# shield_bigfpga.net
KiCad netlist of a schematic drawn in EAGLE
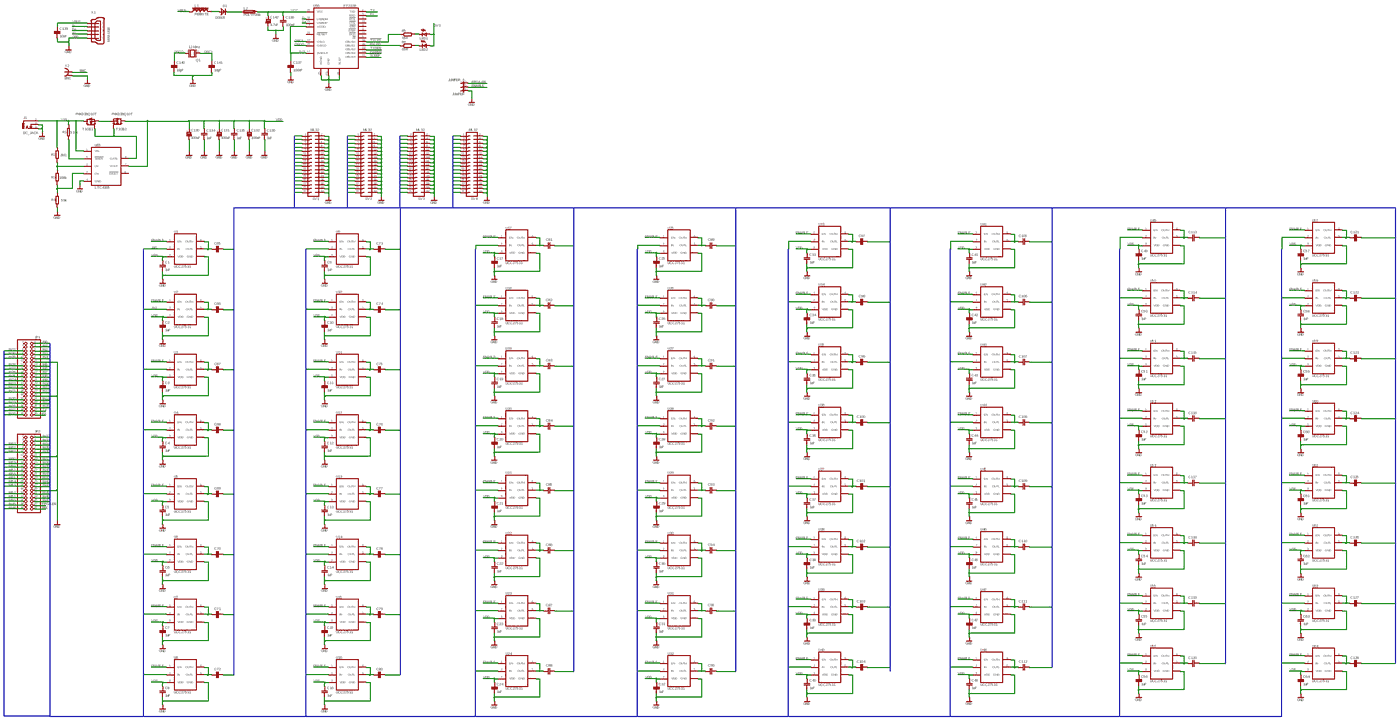
[diagram p0: schematic, sheet 1, overview]
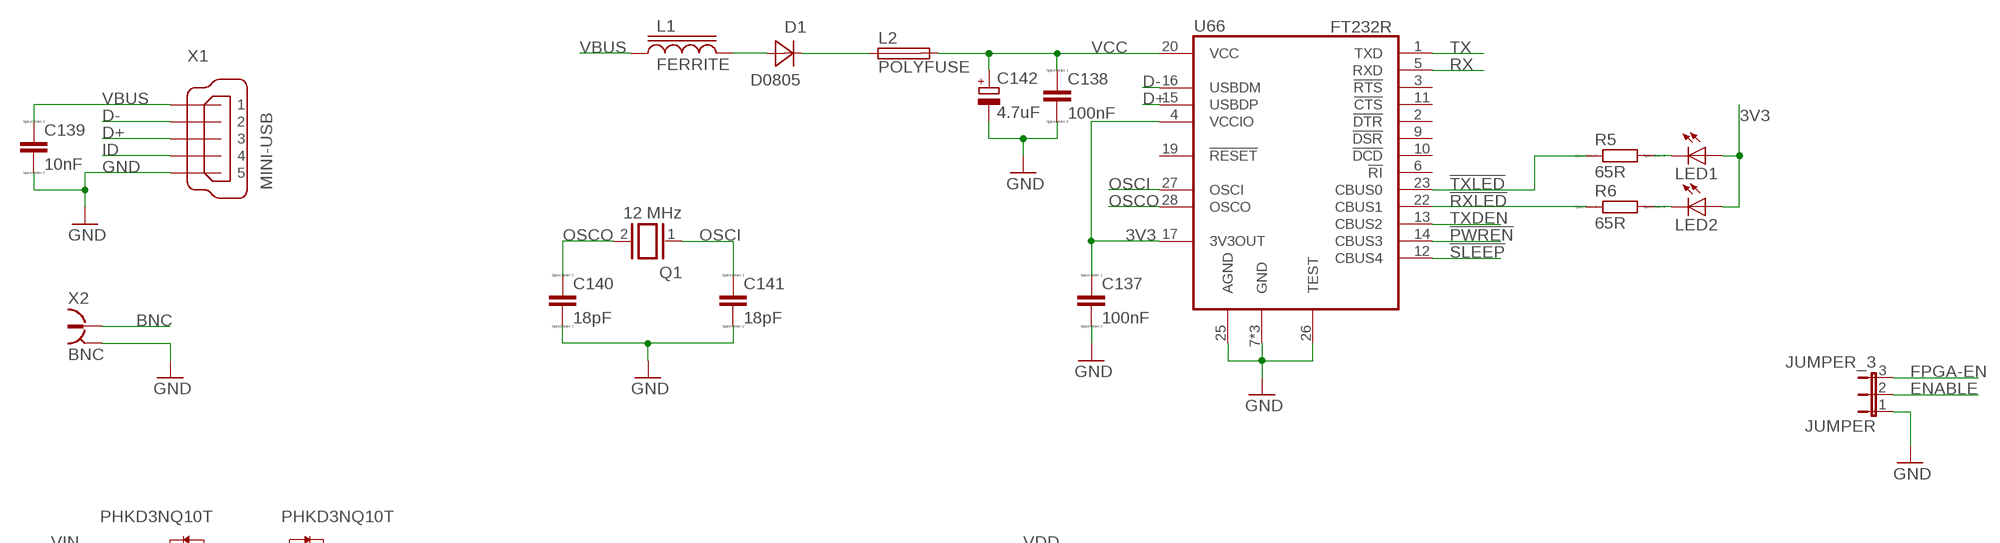
[diagram p1: schematic, sheet 1, part 1 of 4]
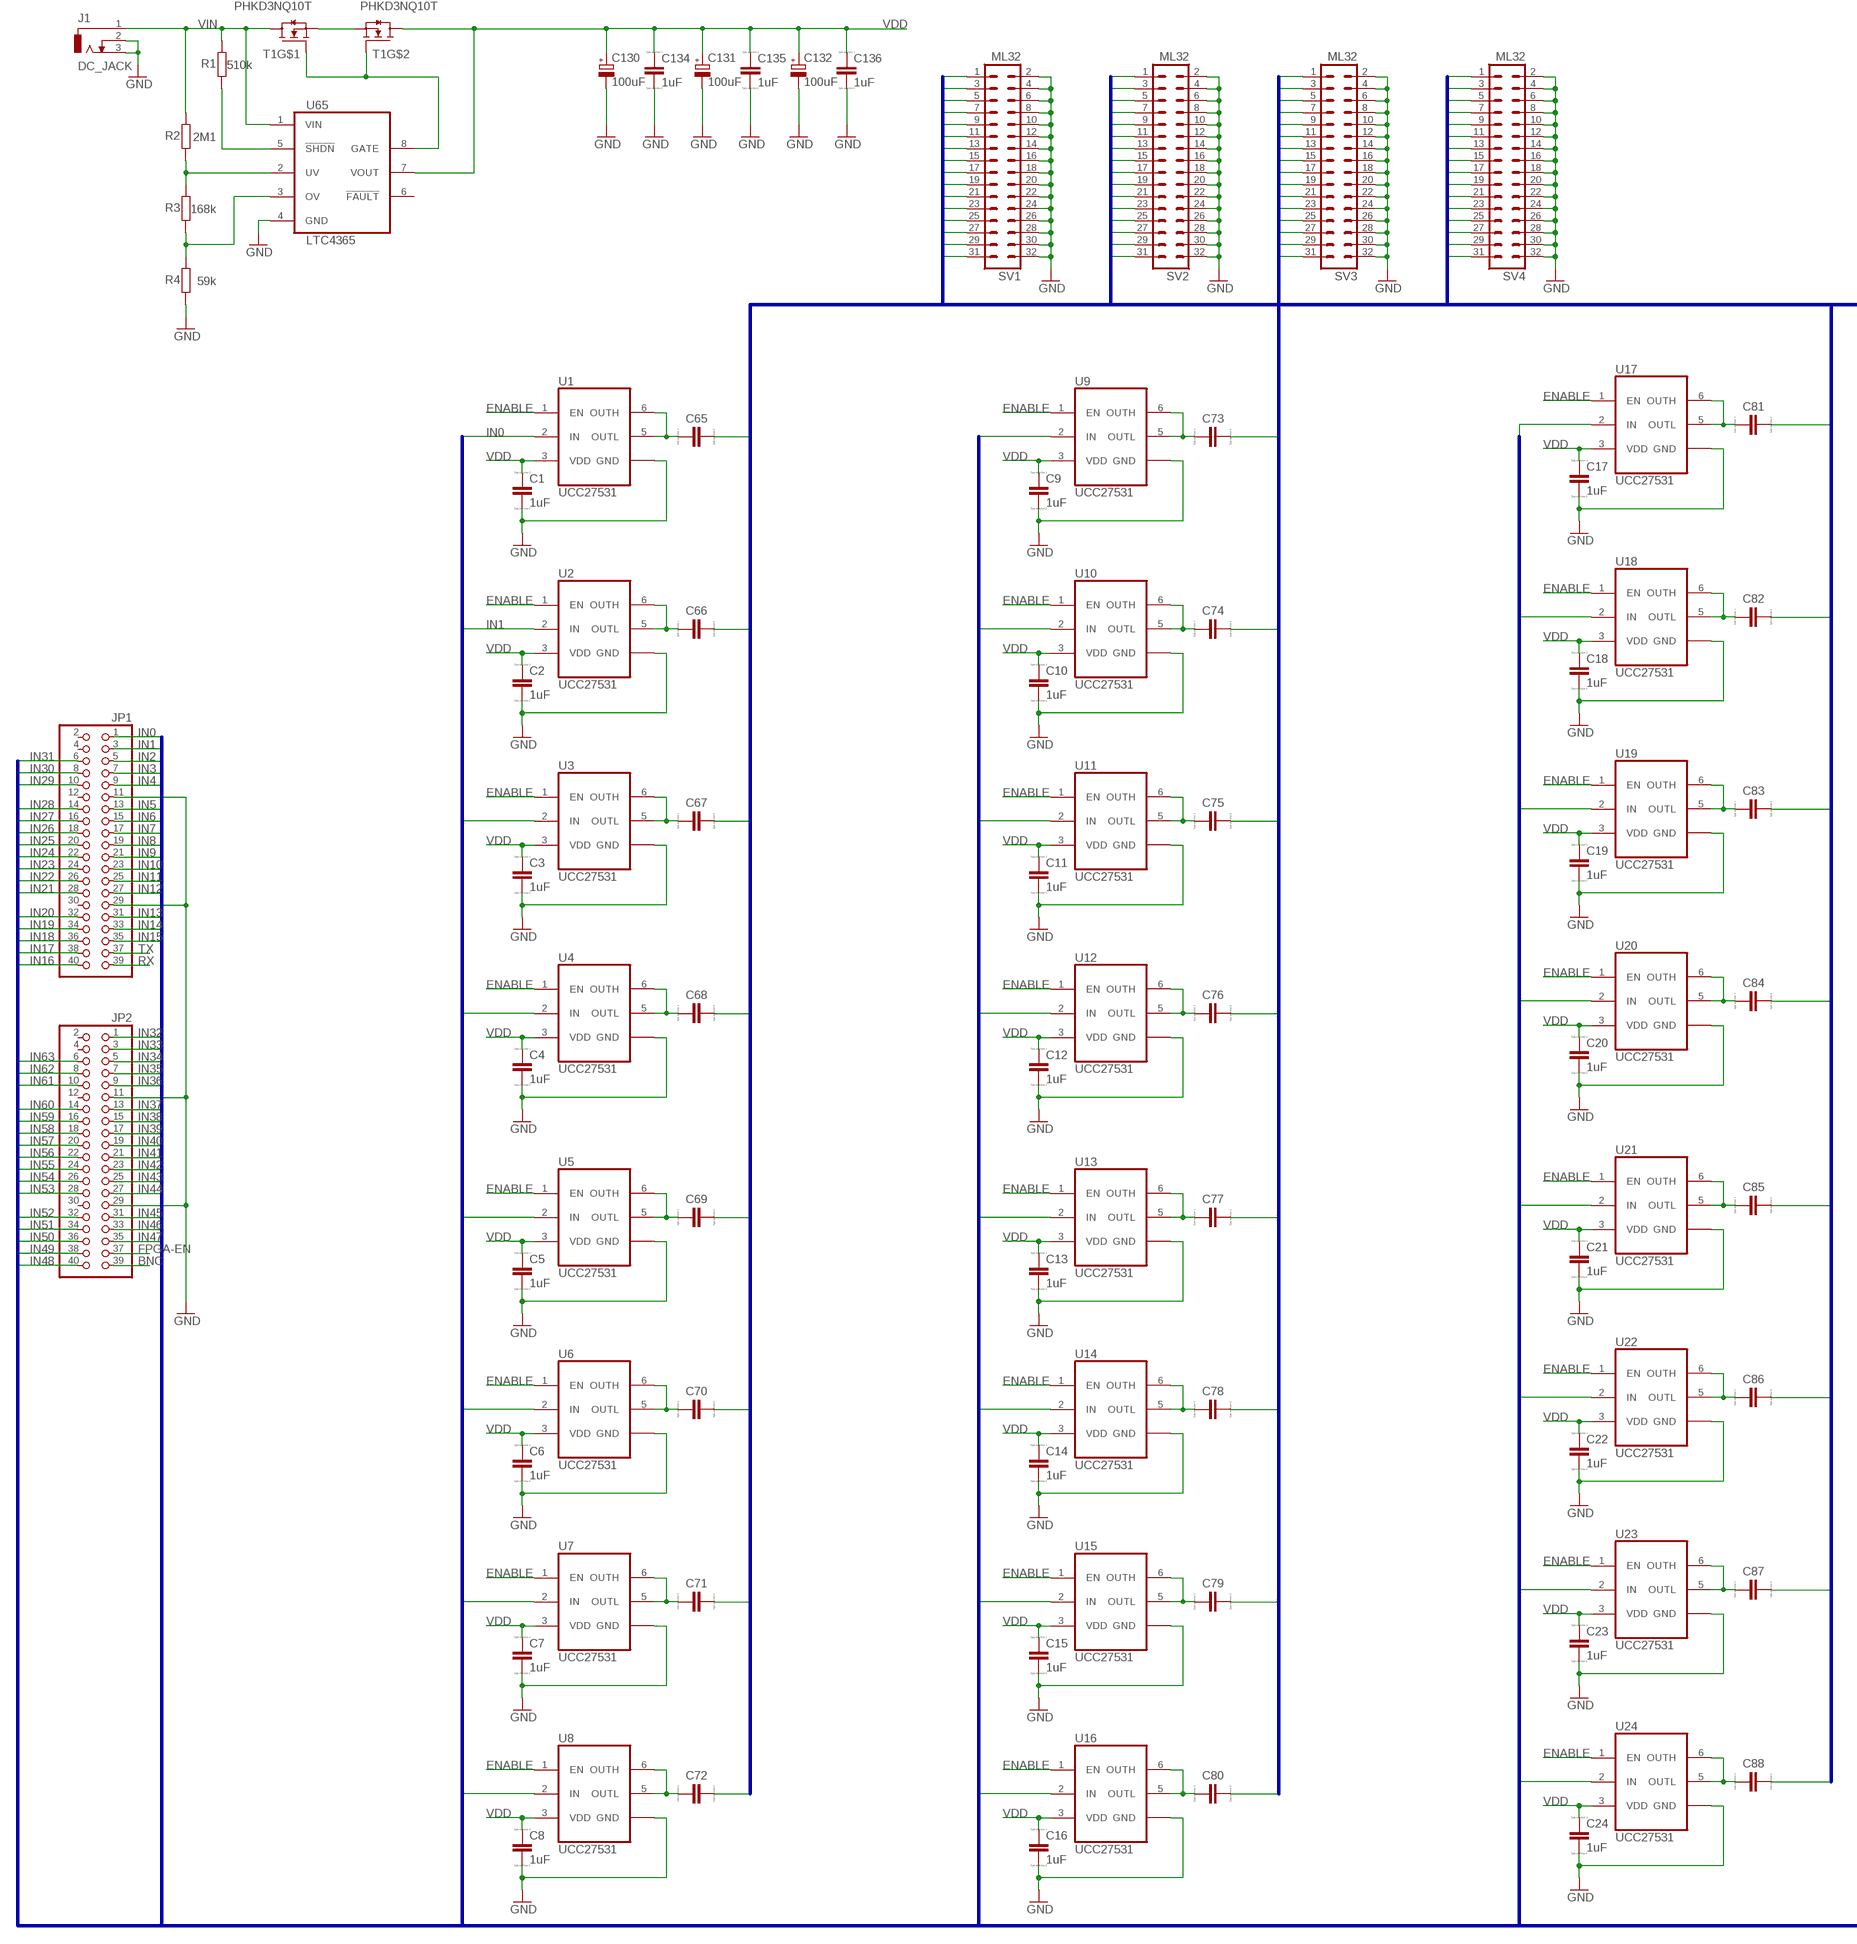
[diagram p2: schematic, sheet 1, part 2 of 4]
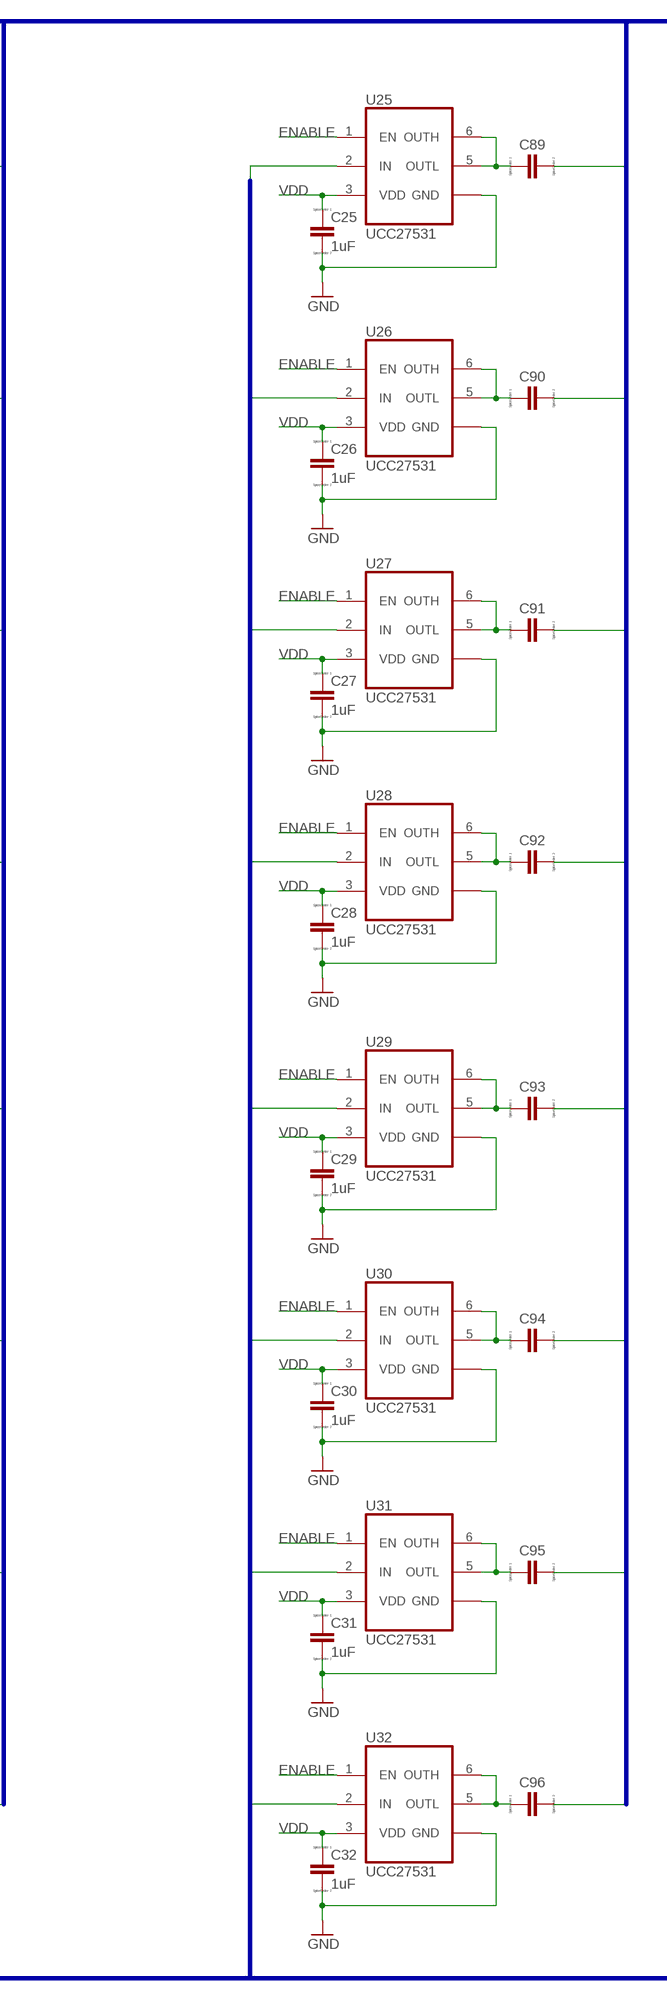
[diagram p3: schematic, sheet 1, part 3 of 4]
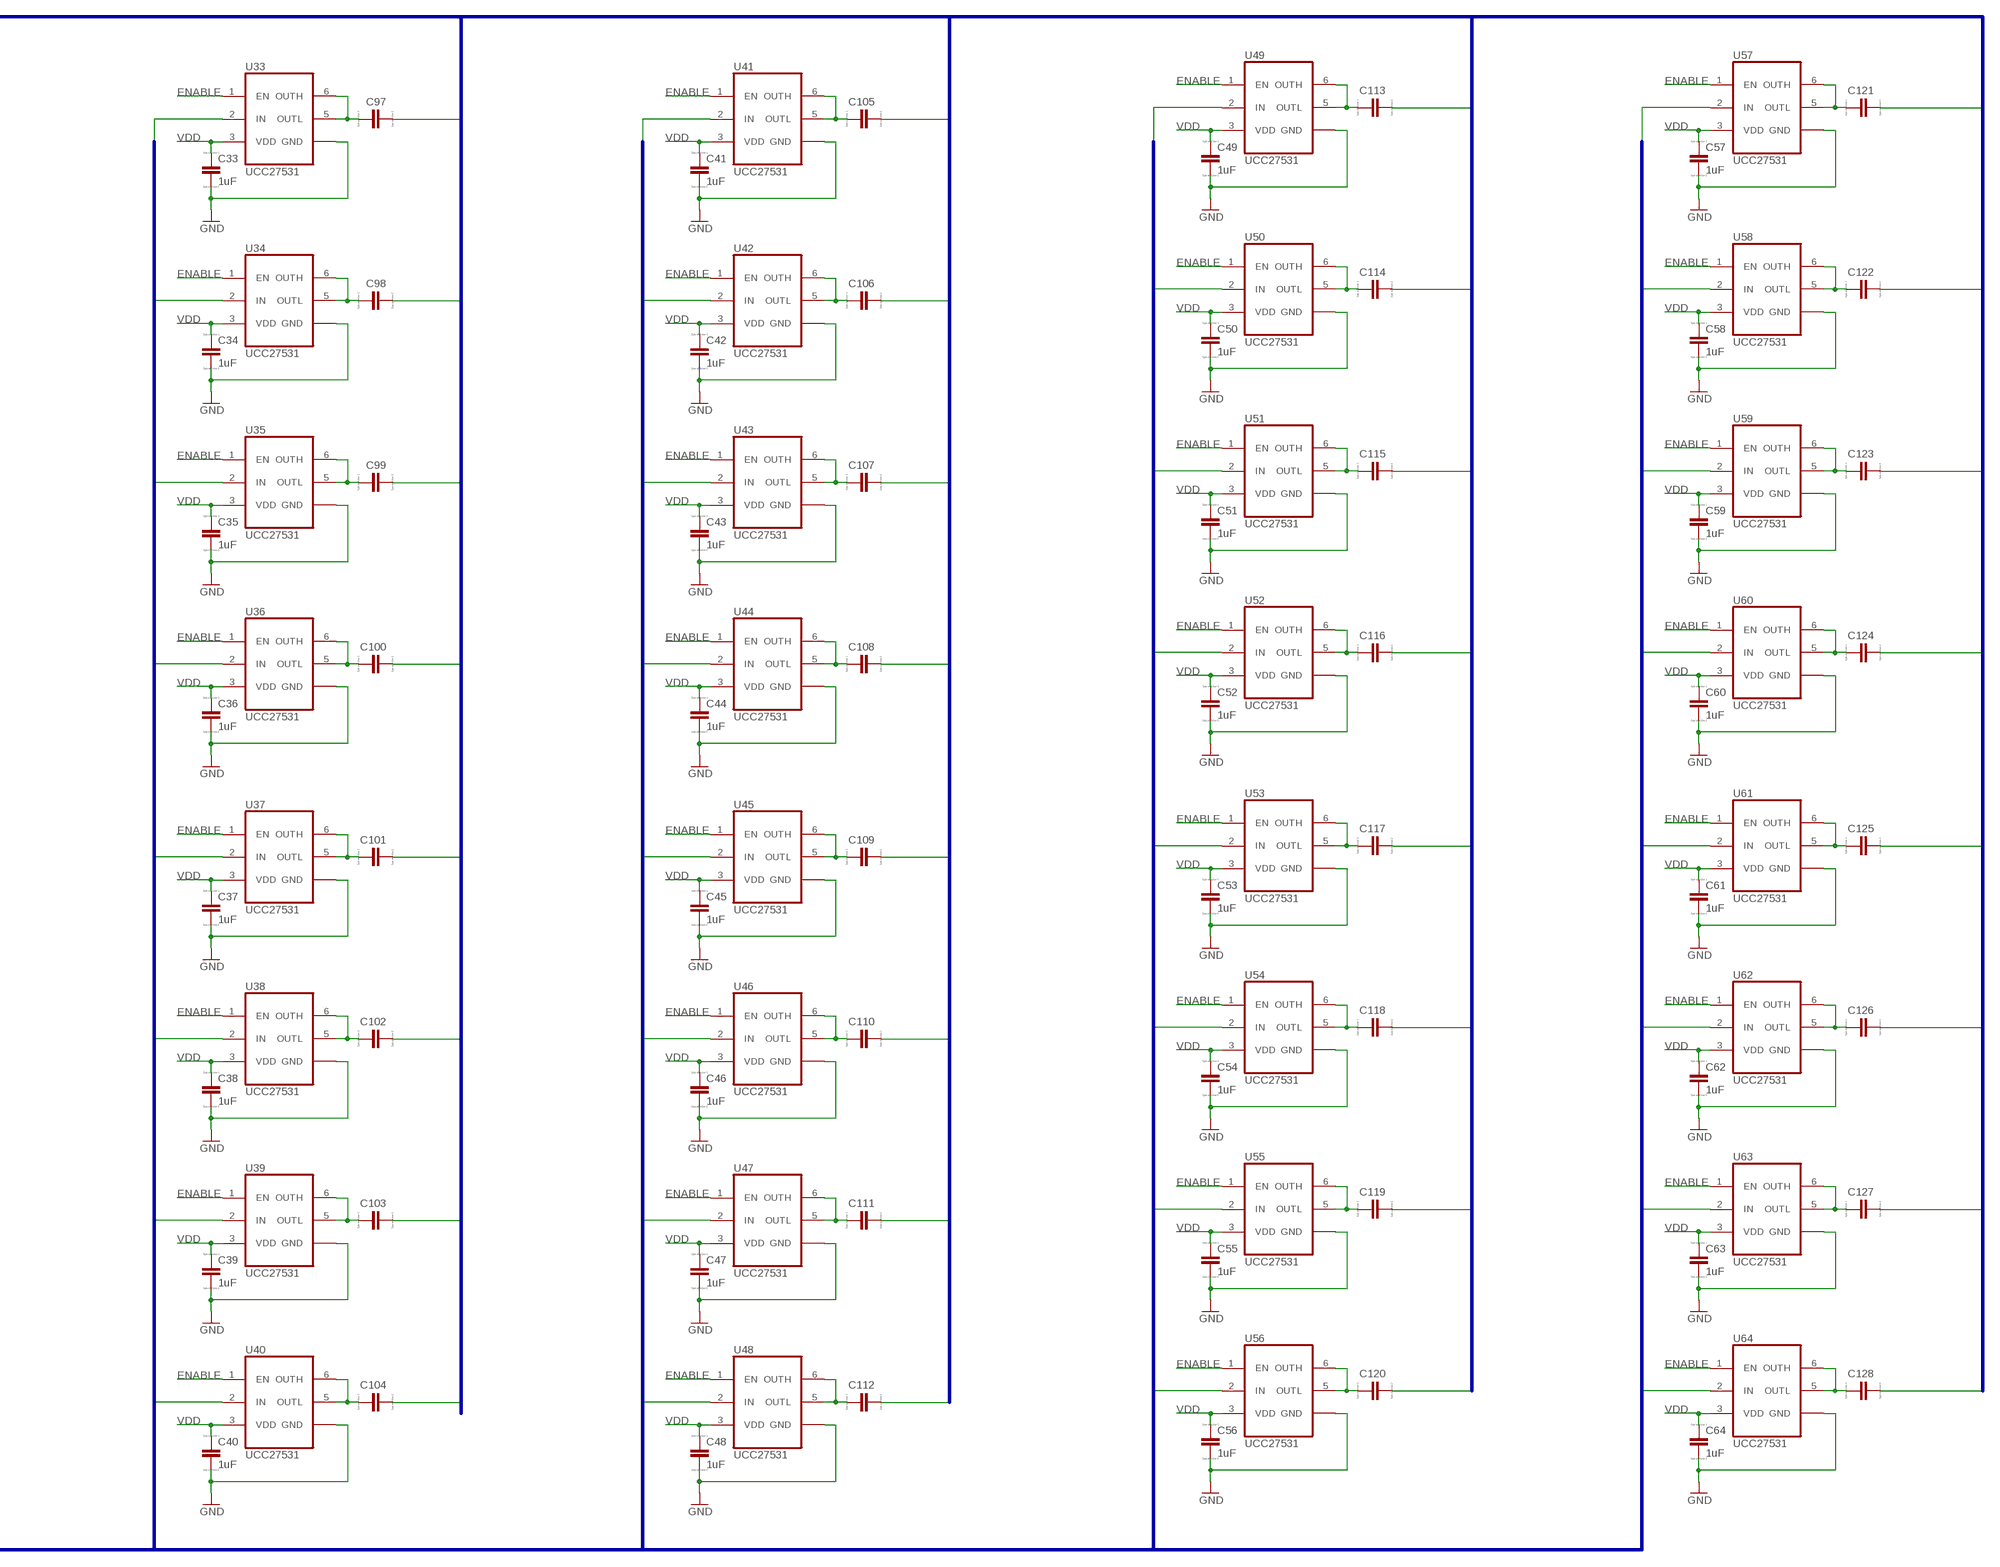
[diagram p4: schematic, sheet 1, part 4 of 4]

(export (version "E")
  (design (tool "Eeschema 10.0.6"))
  (components
    (comp (ref "C1")
      (value "1uF")
      (footprint "eagle-import:C0805")
      (libsource (lib "eagle-import") (part "C"))
    )
    (comp (ref "C2")
      (value "1uF")
      (footprint "eagle-import:C0805")
      (libsource (lib "eagle-import") (part "C"))
    )
    (comp (ref "C3")
      (value "1uF")
      (footprint "eagle-import:C0805")
      (libsource (lib "eagle-import") (part "C"))
    )
    (comp (ref "C4")
      (value "1uF")
      (footprint "eagle-import:C0805")
      (libsource (lib "eagle-import") (part "C"))
    )
    (comp (ref "C5")
      (value "1uF")
      (footprint "eagle-import:C0805")
      (libsource (lib "eagle-import") (part "C"))
    )
    (comp (ref "C6")
      (value "1uF")
      (footprint "eagle-import:C0805")
      (libsource (lib "eagle-import") (part "C"))
    )
    (comp (ref "C7")
      (value "1uF")
      (footprint "eagle-import:C0805")
      (libsource (lib "eagle-import") (part "C"))
    )
    (comp (ref "C8")
      (value "1uF")
      (footprint "eagle-import:C0805")
      (libsource (lib "eagle-import") (part "C"))
    )
    (comp (ref "C9")
      (value "1uF")
      (footprint "eagle-import:C0805")
      (libsource (lib "eagle-import") (part "C"))
    )
    (comp (ref "C10")
      (value "1uF")
      (footprint "eagle-import:C0805")
      (libsource (lib "eagle-import") (part "C"))
    )
    (comp (ref "C11")
      (value "1uF")
      (footprint "eagle-import:C0805")
      (libsource (lib "eagle-import") (part "C"))
    )
    (comp (ref "C12")
      (value "1uF")
      (footprint "eagle-import:C0805")
      (libsource (lib "eagle-import") (part "C"))
    )
    (comp (ref "C13")
      (value "1uF")
      (footprint "eagle-import:C0805")
      (libsource (lib "eagle-import") (part "C"))
    )
    (comp (ref "C14")
      (value "1uF")
      (footprint "eagle-import:C0805")
      (libsource (lib "eagle-import") (part "C"))
    )
    (comp (ref "C15")
      (value "1uF")
      (footprint "eagle-import:C0805")
      (libsource (lib "eagle-import") (part "C"))
    )
    (comp (ref "C16")
      (value "1uF")
      (footprint "eagle-import:C0805")
      (libsource (lib "eagle-import") (part "C"))
    )
    (comp (ref "C17")
      (value "1uF")
      (footprint "eagle-import:C0805")
      (libsource (lib "eagle-import") (part "C"))
    )
    (comp (ref "C18")
      (value "1uF")
      (footprint "eagle-import:C0805")
      (libsource (lib "eagle-import") (part "C"))
    )
    (comp (ref "C19")
      (value "1uF")
      (footprint "eagle-import:C0805")
      (libsource (lib "eagle-import") (part "C"))
    )
    (comp (ref "C20")
      (value "1uF")
      (footprint "eagle-import:C0805")
      (libsource (lib "eagle-import") (part "C"))
    )
    (comp (ref "C21")
      (value "1uF")
      (footprint "eagle-import:C0805")
      (libsource (lib "eagle-import") (part "C"))
    )
    (comp (ref "C22")
      (value "1uF")
      (footprint "eagle-import:C0805")
      (libsource (lib "eagle-import") (part "C"))
    )
    (comp (ref "C23")
      (value "1uF")
      (footprint "eagle-import:C0805")
      (libsource (lib "eagle-import") (part "C"))
    )
    (comp (ref "C24")
      (value "1uF")
      (footprint "eagle-import:C0805")
      (libsource (lib "eagle-import") (part "C"))
    )
    (comp (ref "C25")
      (value "1uF")
      (footprint "eagle-import:C0805")
      (libsource (lib "eagle-import") (part "C"))
    )
    (comp (ref "C26")
      (value "1uF")
      (footprint "eagle-import:C0805")
      (libsource (lib "eagle-import") (part "C"))
    )
    (comp (ref "C27")
      (value "1uF")
      (footprint "eagle-import:C0805")
      (libsource (lib "eagle-import") (part "C"))
    )
    (comp (ref "C28")
      (value "1uF")
      (footprint "eagle-import:C0805")
      (libsource (lib "eagle-import") (part "C"))
    )
    (comp (ref "C29")
      (value "1uF")
      (footprint "eagle-import:C0805")
      (libsource (lib "eagle-import") (part "C"))
    )
    (comp (ref "C30")
      (value "1uF")
      (footprint "eagle-import:C0805")
      (libsource (lib "eagle-import") (part "C"))
    )
    (comp (ref "C31")
      (value "1uF")
      (footprint "eagle-import:C0805")
      (libsource (lib "eagle-import") (part "C"))
    )
    (comp (ref "C32")
      (value "1uF")
      (footprint "eagle-import:C0805")
      (libsource (lib "eagle-import") (part "C"))
    )
    (comp (ref "C33")
      (value "1uF")
      (footprint "eagle-import:C0805")
      (libsource (lib "eagle-import") (part "C"))
    )
    (comp (ref "C34")
      (value "1uF")
      (footprint "eagle-import:C0805")
      (libsource (lib "eagle-import") (part "C"))
    )
    (comp (ref "C35")
      (value "1uF")
      (footprint "eagle-import:C0805")
      (libsource (lib "eagle-import") (part "C"))
    )
    (comp (ref "C36")
      (value "1uF")
      (footprint "eagle-import:C0805")
      (libsource (lib "eagle-import") (part "C"))
    )
    (comp (ref "C37")
      (value "1uF")
      (footprint "eagle-import:C0805")
      (libsource (lib "eagle-import") (part "C"))
    )
    (comp (ref "C38")
      (value "1uF")
      (footprint "eagle-import:C0805")
      (libsource (lib "eagle-import") (part "C"))
    )
    (comp (ref "C39")
      (value "1uF")
      (footprint "eagle-import:C0805")
      (libsource (lib "eagle-import") (part "C"))
    )
    (comp (ref "C40")
      (value "1uF")
      (footprint "eagle-import:C0805")
      (libsource (lib "eagle-import") (part "C"))
    )
    (comp (ref "C41")
      (value "1uF")
      (footprint "eagle-import:C0805")
      (libsource (lib "eagle-import") (part "C"))
    )
    (comp (ref "C42")
      (value "1uF")
      (footprint "eagle-import:C0805")
      (libsource (lib "eagle-import") (part "C"))
    )
    (comp (ref "C43")
      (value "1uF")
      (footprint "eagle-import:C0805")
      (libsource (lib "eagle-import") (part "C"))
    )
    (comp (ref "C44")
      (value "1uF")
      (footprint "eagle-import:C0805")
      (libsource (lib "eagle-import") (part "C"))
    )
    (comp (ref "C45")
      (value "1uF")
      (footprint "eagle-import:C0805")
      (libsource (lib "eagle-import") (part "C"))
    )
    (comp (ref "C46")
      (value "1uF")
      (footprint "eagle-import:C0805")
      (libsource (lib "eagle-import") (part "C"))
    )
    (comp (ref "C47")
      (value "1uF")
      (footprint "eagle-import:C0805")
      (libsource (lib "eagle-import") (part "C"))
    )
    (comp (ref "C48")
      (value "1uF")
      (footprint "eagle-import:C0805")
      (libsource (lib "eagle-import") (part "C"))
    )
    (comp (ref "C49")
      (value "1uF")
      (footprint "eagle-import:C0805")
      (libsource (lib "eagle-import") (part "C"))
    )
    (comp (ref "C50")
      (value "1uF")
      (footprint "eagle-import:C0805")
      (libsource (lib "eagle-import") (part "C"))
    )
    (comp (ref "C51")
      (value "1uF")
      (footprint "eagle-import:C0805")
      (libsource (lib "eagle-import") (part "C"))
    )
    (comp (ref "C52")
      (value "1uF")
      (footprint "eagle-import:C0805")
      (libsource (lib "eagle-import") (part "C"))
    )
    (comp (ref "C53")
      (value "1uF")
      (footprint "eagle-import:C0805")
      (libsource (lib "eagle-import") (part "C"))
    )
    (comp (ref "C54")
      (value "1uF")
      (footprint "eagle-import:C0805")
      (libsource (lib "eagle-import") (part "C"))
    )
    (comp (ref "C55")
      (value "1uF")
      (footprint "eagle-import:C0805")
      (libsource (lib "eagle-import") (part "C"))
    )
    (comp (ref "C56")
      (value "1uF")
      (footprint "eagle-import:C0805")
      (libsource (lib "eagle-import") (part "C"))
    )
    (comp (ref "C57")
      (value "1uF")
      (footprint "eagle-import:C0805")
      (libsource (lib "eagle-import") (part "C"))
    )
    (comp (ref "C58")
      (value "1uF")
      (footprint "eagle-import:C0805")
      (libsource (lib "eagle-import") (part "C"))
    )
    (comp (ref "C59")
      (value "1uF")
      (footprint "eagle-import:C0805")
      (libsource (lib "eagle-import") (part "C"))
    )
    (comp (ref "C60")
      (value "1uF")
      (footprint "eagle-import:C0805")
      (libsource (lib "eagle-import") (part "C"))
    )
    (comp (ref "C61")
      (value "1uF")
      (footprint "eagle-import:C0805")
      (libsource (lib "eagle-import") (part "C"))
    )
    (comp (ref "C62")
      (value "1uF")
      (footprint "eagle-import:C0805")
      (libsource (lib "eagle-import") (part "C"))
    )
    (comp (ref "C63")
      (value "1uF")
      (footprint "eagle-import:C0805")
      (libsource (lib "eagle-import") (part "C"))
    )
    (comp (ref "C64")
      (value "1uF")
      (footprint "eagle-import:C0805")
      (libsource (lib "eagle-import") (part "C"))
    )
    (comp (ref "C65")
      (value "C")
      (footprint "eagle-import:C0805")
      (libsource (lib "eagle-import") (part "C"))
    )
    (comp (ref "C66")
      (value "C")
      (footprint "eagle-import:C0805")
      (libsource (lib "eagle-import") (part "C"))
    )
    (comp (ref "C67")
      (value "C")
      (footprint "eagle-import:C0805")
      (libsource (lib "eagle-import") (part "C"))
    )
    (comp (ref "C68")
      (value "C")
      (footprint "eagle-import:C0805")
      (libsource (lib "eagle-import") (part "C"))
    )
    (comp (ref "C69")
      (value "C")
      (footprint "eagle-import:C0805")
      (libsource (lib "eagle-import") (part "C"))
    )
    (comp (ref "C70")
      (value "C")
      (footprint "eagle-import:C0805")
      (libsource (lib "eagle-import") (part "C"))
    )
    (comp (ref "C71")
      (value "C")
      (footprint "eagle-import:C0805")
      (libsource (lib "eagle-import") (part "C"))
    )
    (comp (ref "C72")
      (value "C")
      (footprint "eagle-import:C0805")
      (libsource (lib "eagle-import") (part "C"))
    )
    (comp (ref "C73")
      (value "C")
      (footprint "eagle-import:C0805")
      (libsource (lib "eagle-import") (part "C"))
    )
    (comp (ref "C74")
      (value "C")
      (footprint "eagle-import:C0805")
      (libsource (lib "eagle-import") (part "C"))
    )
    (comp (ref "C75")
      (value "C")
      (footprint "eagle-import:C0805")
      (libsource (lib "eagle-import") (part "C"))
    )
    (comp (ref "C76")
      (value "C")
      (footprint "eagle-import:C0805")
      (libsource (lib "eagle-import") (part "C"))
    )
    (comp (ref "C77")
      (value "C")
      (footprint "eagle-import:C0805")
      (libsource (lib "eagle-import") (part "C"))
    )
    (comp (ref "C78")
      (value "C")
      (footprint "eagle-import:C0805")
      (libsource (lib "eagle-import") (part "C"))
    )
    (comp (ref "C79")
      (value "C")
      (footprint "eagle-import:C0805")
      (libsource (lib "eagle-import") (part "C"))
    )
    (comp (ref "C80")
      (value "C")
      (footprint "eagle-import:C0805")
      (libsource (lib "eagle-import") (part "C"))
    )
    (comp (ref "C81")
      (value "C")
      (footprint "eagle-import:C0805")
      (libsource (lib "eagle-import") (part "C"))
    )
    (comp (ref "C82")
      (value "C")
      (footprint "eagle-import:C0805")
      (libsource (lib "eagle-import") (part "C"))
    )
    (comp (ref "C83")
      (value "C")
      (footprint "eagle-import:C0805")
      (libsource (lib "eagle-import") (part "C"))
    )
    (comp (ref "C84")
      (value "C")
      (footprint "eagle-import:C0805")
      (libsource (lib "eagle-import") (part "C"))
    )
    (comp (ref "C85")
      (value "C")
      (footprint "eagle-import:C0805")
      (libsource (lib "eagle-import") (part "C"))
    )
    (comp (ref "C86")
      (value "C")
      (footprint "eagle-import:C0805")
      (libsource (lib "eagle-import") (part "C"))
    )
    (comp (ref "C87")
      (value "C")
      (footprint "eagle-import:C0805")
      (libsource (lib "eagle-import") (part "C"))
    )
    (comp (ref "C88")
      (value "C")
      (footprint "eagle-import:C0805")
      (libsource (lib "eagle-import") (part "C"))
    )
    (comp (ref "C89")
      (value "C")
      (footprint "eagle-import:C0805")
      (libsource (lib "eagle-import") (part "C"))
    )
    (comp (ref "C90")
      (value "C")
      (footprint "eagle-import:C0805")
      (libsource (lib "eagle-import") (part "C"))
    )
    (comp (ref "C91")
      (value "C")
      (footprint "eagle-import:C0805")
      (libsource (lib "eagle-import") (part "C"))
    )
    (comp (ref "C92")
      (value "C")
      (footprint "eagle-import:C0805")
      (libsource (lib "eagle-import") (part "C"))
    )
    (comp (ref "C93")
      (value "C")
      (footprint "eagle-import:C0805")
      (libsource (lib "eagle-import") (part "C"))
    )
    (comp (ref "C94")
      (value "C")
      (footprint "eagle-import:C0805")
      (libsource (lib "eagle-import") (part "C"))
    )
    (comp (ref "C95")
      (value "C")
      (footprint "eagle-import:C0805")
      (libsource (lib "eagle-import") (part "C"))
    )
    (comp (ref "C96")
      (value "C")
      (footprint "eagle-import:C0805")
      (libsource (lib "eagle-import") (part "C"))
    )
    (comp (ref "C97")
      (value "C")
      (footprint "eagle-import:C0805")
      (libsource (lib "eagle-import") (part "C"))
    )
    (comp (ref "C98")
      (value "C")
      (footprint "eagle-import:C0805")
      (libsource (lib "eagle-import") (part "C"))
    )
    (comp (ref "C99")
      (value "C")
      (footprint "eagle-import:C0805")
      (libsource (lib "eagle-import") (part "C"))
    )
    (comp (ref "C100")
      (value "C")
      (footprint "eagle-import:C0805")
      (libsource (lib "eagle-import") (part "C"))
    )
    (comp (ref "C101")
      (value "C")
      (footprint "eagle-import:C0805")
      (libsource (lib "eagle-import") (part "C"))
    )
    (comp (ref "C102")
      (value "C")
      (footprint "eagle-import:C0805")
      (libsource (lib "eagle-import") (part "C"))
    )
    (comp (ref "C103")
      (value "C")
      (footprint "eagle-import:C0805")
      (libsource (lib "eagle-import") (part "C"))
    )
    (comp (ref "C104")
      (value "C")
      (footprint "eagle-import:C0805")
      (libsource (lib "eagle-import") (part "C"))
    )
    (comp (ref "C105")
      (value "C")
      (footprint "eagle-import:C0805")
      (libsource (lib "eagle-import") (part "C"))
    )
    (comp (ref "C106")
      (value "C")
      (footprint "eagle-import:C0805")
      (libsource (lib "eagle-import") (part "C"))
    )
    (comp (ref "C107")
      (value "C")
      (footprint "eagle-import:C0805")
      (libsource (lib "eagle-import") (part "C"))
    )
    (comp (ref "C108")
      (value "C")
      (footprint "eagle-import:C0805")
      (libsource (lib "eagle-import") (part "C"))
    )
    (comp (ref "C109")
      (value "C")
      (footprint "eagle-import:C0805")
      (libsource (lib "eagle-import") (part "C"))
    )
    (comp (ref "C110")
      (value "C")
      (footprint "eagle-import:C0805")
      (libsource (lib "eagle-import") (part "C"))
    )
    (comp (ref "C111")
      (value "C")
      (footprint "eagle-import:C0805")
      (libsource (lib "eagle-import") (part "C"))
    )
    (comp (ref "C112")
      (value "C")
      (footprint "eagle-import:C0805")
      (libsource (lib "eagle-import") (part "C"))
    )
    (comp (ref "C113")
      (value "C")
      (footprint "eagle-import:C0805")
      (libsource (lib "eagle-import") (part "C"))
    )
    (comp (ref "C114")
      (value "C")
      (footprint "eagle-import:C0805")
      (libsource (lib "eagle-import") (part "C"))
    )
    (comp (ref "C115")
      (value "C")
      (footprint "eagle-import:C0805")
      (libsource (lib "eagle-import") (part "C"))
    )
    (comp (ref "C116")
      (value "C")
      (footprint "eagle-import:C0805")
      (libsource (lib "eagle-import") (part "C"))
    )
    (comp (ref "C117")
      (value "C")
      (footprint "eagle-import:C0805")
      (libsource (lib "eagle-import") (part "C"))
    )
    (comp (ref "C118")
      (value "C")
      (footprint "eagle-import:C0805")
      (libsource (lib "eagle-import") (part "C"))
    )
    (comp (ref "C119")
      (value "C")
      (footprint "eagle-import:C0805")
      (libsource (lib "eagle-import") (part "C"))
    )
    (comp (ref "C120")
      (value "C")
      (footprint "eagle-import:C0805")
      (libsource (lib "eagle-import") (part "C"))
    )
    (comp (ref "C121")
      (value "C")
      (footprint "eagle-import:C0805")
      (libsource (lib "eagle-import") (part "C"))
    )
    (comp (ref "C122")
      (value "C")
      (footprint "eagle-import:C0805")
      (libsource (lib "eagle-import") (part "C"))
    )
    (comp (ref "C123")
      (value "C")
      (footprint "eagle-import:C0805")
      (libsource (lib "eagle-import") (part "C"))
    )
    (comp (ref "C124")
      (value "C")
      (footprint "eagle-import:C0805")
      (libsource (lib "eagle-import") (part "C"))
    )
    (comp (ref "C125")
      (value "C")
      (footprint "eagle-import:C0805")
      (libsource (lib "eagle-import") (part "C"))
    )
    (comp (ref "C126")
      (value "C")
      (footprint "eagle-import:C0805")
      (libsource (lib "eagle-import") (part "C"))
    )
    (comp (ref "C127")
      (value "C")
      (footprint "eagle-import:C0805")
      (libsource (lib "eagle-import") (part "C"))
    )
    (comp (ref "C128")
      (value "C")
      (footprint "eagle-import:C0805")
      (libsource (lib "eagle-import") (part "C"))
    )
    (comp (ref "C130")
      (value "100uF")
      (footprint "eagle-import:E5-10,5")
      (libsource (lib "eagle-import") (part "CPOL-EUE5-10.5"))
    )
    (comp (ref "C131")
      (value "100uF")
      (footprint "eagle-import:E5-10,5")
      (libsource (lib "eagle-import") (part "CPOL-EUE5-10.5"))
    )
    (comp (ref "C132")
      (value "100uF")
      (footprint "eagle-import:E5-10,5")
      (libsource (lib "eagle-import") (part "CPOL-EUE5-10.5"))
    )
    (comp (ref "C134")
      (value "1uF")
      (footprint "eagle-import:C0805")
      (libsource (lib "eagle-import") (part "C"))
    )
    (comp (ref "C135")
      (value "1uF")
      (footprint "eagle-import:C0805")
      (libsource (lib "eagle-import") (part "C"))
    )
    (comp (ref "C136")
      (value "1uF")
      (footprint "eagle-import:C0805")
      (libsource (lib "eagle-import") (part "C"))
    )
    (comp (ref "C137")
      (value "100nF")
      (footprint "eagle-import:C0805")
      (libsource (lib "eagle-import") (part "C"))
    )
    (comp (ref "C138")
      (value "100nF")
      (footprint "eagle-import:C0805")
      (libsource (lib "eagle-import") (part "C"))
    )
    (comp (ref "C139")
      (value "10nF")
      (footprint "eagle-import:C0805")
      (libsource (lib "eagle-import") (part "C"))
    )
    (comp (ref "C140")
      (value "18pF")
      (footprint "eagle-import:C0805")
      (libsource (lib "eagle-import") (part "C"))
    )
    (comp (ref "C141")
      (value "18pF")
      (footprint "eagle-import:C0805")
      (libsource (lib "eagle-import") (part "C"))
    )
    (comp (ref "C142")
      (value "4.7uF")
      (footprint "eagle-import:E2,5-6")
      (libsource (lib "eagle-import") (part "CPOL-EUE2.5-6"))
    )
    (comp (ref "D1")
      (value "D0805")
      (footprint "eagle-import:D0805")
      (libsource (lib "eagle-import") (part "D0805"))
    )
    (comp (ref "J1")
      (value "DC_JACK")
      (footprint "eagle-import:DCJ0202")
      (libsource (lib "eagle-import") (part "DC_JACK"))
    )
    (comp (ref "JP1")
      (value "PINHD-2X20")
      (footprint "eagle-import:2X20")
      (libsource (lib "eagle-import") (part "PINHD-2X20"))
    )
    (comp (ref "JP2")
      (value "PINHD-2X20")
      (footprint "eagle-import:2X20")
      (libsource (lib "eagle-import") (part "PINHD-2X20"))
    )
    (comp (ref "JUMPER")
      (value "JUMPER_3")
      (footprint "eagle-import:JP2")
      (libsource (lib "eagle-import") (part "JUMPER_3"))
    )
    (comp (ref "L1")
      (value "FERRITE")
      (footprint "eagle-import:SML0805")
      (libsource (lib "eagle-import") (part "FERRITE"))
    )
    (comp (ref "L2")
      (value "POLYFUSE")
      (footprint "eagle-import:SML0805")
      (libsource (lib "eagle-import") (part "POLYFUSE"))
    )
    (comp (ref "LED1")
      (value "LEDSML1206")
      (footprint "eagle-import:SML1206")
      (libsource (lib "eagle-import") (part "LEDSML1206"))
    )
    (comp (ref "LED2")
      (value "LEDSML1206")
      (footprint "eagle-import:SML1206")
      (libsource (lib "eagle-import") (part "LEDSML1206"))
    )
    (comp (ref "Q1")
      (value "12 MHz")
      (footprint "eagle-import:QS")
      (libsource (lib "eagle-import") (part "XTAL/S"))
    )
    (comp (ref "R1")
      (value "510k")
      (footprint "eagle-import:R0805")
      (libsource (lib "eagle-import") (part "R-EU_R0805"))
    )
    (comp (ref "R2")
      (value "2M1")
      (footprint "eagle-import:R0805")
      (libsource (lib "eagle-import") (part "R-EU_R0805"))
    )
    (comp (ref "R3")
      (value "168k")
      (footprint "eagle-import:R0805")
      (libsource (lib "eagle-import") (part "R-EU_R0805"))
    )
    (comp (ref "R4")
      (value "59k")
      (footprint "eagle-import:R0805")
      (libsource (lib "eagle-import") (part "R-EU_R0805"))
    )
    (comp (ref "R5")
      (value "65R")
      (footprint "eagle-import:R0805")
      (libsource (lib "eagle-import") (part "R"))
    )
    (comp (ref "R6")
      (value "65R")
      (footprint "eagle-import:R0805")
      (libsource (lib "eagle-import") (part "R"))
    )
    (comp (ref "SV1")
      (value "ML32")
      (footprint "eagle-import:ML32")
      (libsource (lib "eagle-import") (part "ML32"))
    )
    (comp (ref "SV2")
      (value "ML32")
      (footprint "eagle-import:ML32")
      (libsource (lib "eagle-import") (part "ML32"))
    )
    (comp (ref "SV3")
      (value "ML32")
      (footprint "eagle-import:ML32")
      (libsource (lib "eagle-import") (part "ML32"))
    )
    (comp (ref "SV4")
      (value "ML32")
      (footprint "eagle-import:ML32")
      (libsource (lib "eagle-import") (part "ML32"))
    )
    (comp (ref "T1")
      (value "PHKD3NQ10T")
      (footprint "eagle-import:SO8")
      (libsource (lib "eagle-import") (part "PHKD3NQ10T"))
    )
    (comp (ref "U1")
      (value "UCC27531")
      (footprint "eagle-import:DBV_R-PDSO-G6")
      (libsource (lib "eagle-import") (part "UCC27531"))
    )
    (comp (ref "U2")
      (value "UCC27531")
      (footprint "eagle-import:DBV_R-PDSO-G6")
      (libsource (lib "eagle-import") (part "UCC27531"))
    )
    (comp (ref "U3")
      (value "UCC27531")
      (footprint "eagle-import:DBV_R-PDSO-G6")
      (libsource (lib "eagle-import") (part "UCC27531"))
    )
    (comp (ref "U4")
      (value "UCC27531")
      (footprint "eagle-import:DBV_R-PDSO-G6")
      (libsource (lib "eagle-import") (part "UCC27531"))
    )
    (comp (ref "U5")
      (value "UCC27531")
      (footprint "eagle-import:DBV_R-PDSO-G6")
      (libsource (lib "eagle-import") (part "UCC27531"))
    )
    (comp (ref "U6")
      (value "UCC27531")
      (footprint "eagle-import:DBV_R-PDSO-G6")
      (libsource (lib "eagle-import") (part "UCC27531"))
    )
    (comp (ref "U7")
      (value "UCC27531")
      (footprint "eagle-import:DBV_R-PDSO-G6")
      (libsource (lib "eagle-import") (part "UCC27531"))
    )
    (comp (ref "U8")
      (value "UCC27531")
      (footprint "eagle-import:DBV_R-PDSO-G6")
      (libsource (lib "eagle-import") (part "UCC27531"))
    )
    (comp (ref "U9")
      (value "UCC27531")
      (footprint "eagle-import:DBV_R-PDSO-G6")
      (libsource (lib "eagle-import") (part "UCC27531"))
    )
    (comp (ref "U10")
      (value "UCC27531")
      (footprint "eagle-import:DBV_R-PDSO-G6")
      (libsource (lib "eagle-import") (part "UCC27531"))
    )
    (comp (ref "U11")
      (value "UCC27531")
      (footprint "eagle-import:DBV_R-PDSO-G6")
      (libsource (lib "eagle-import") (part "UCC27531"))
    )
    (comp (ref "U12")
      (value "UCC27531")
      (footprint "eagle-import:DBV_R-PDSO-G6")
      (libsource (lib "eagle-import") (part "UCC27531"))
    )
    (comp (ref "U13")
      (value "UCC27531")
      (footprint "eagle-import:DBV_R-PDSO-G6")
      (libsource (lib "eagle-import") (part "UCC27531"))
    )
    (comp (ref "U14")
      (value "UCC27531")
      (footprint "eagle-import:DBV_R-PDSO-G6")
      (libsource (lib "eagle-import") (part "UCC27531"))
    )
    (comp (ref "U15")
      (value "UCC27531")
      (footprint "eagle-import:DBV_R-PDSO-G6")
      (libsource (lib "eagle-import") (part "UCC27531"))
    )
    (comp (ref "U16")
      (value "UCC27531")
      (footprint "eagle-import:DBV_R-PDSO-G6")
      (libsource (lib "eagle-import") (part "UCC27531"))
    )
    (comp (ref "U17")
      (value "UCC27531")
      (footprint "eagle-import:DBV_R-PDSO-G6")
      (libsource (lib "eagle-import") (part "UCC27531"))
    )
    (comp (ref "U18")
      (value "UCC27531")
      (footprint "eagle-import:DBV_R-PDSO-G6")
      (libsource (lib "eagle-import") (part "UCC27531"))
    )
    (comp (ref "U19")
      (value "UCC27531")
      (footprint "eagle-import:DBV_R-PDSO-G6")
      (libsource (lib "eagle-import") (part "UCC27531"))
    )
    (comp (ref "U20")
      (value "UCC27531")
      (footprint "eagle-import:DBV_R-PDSO-G6")
      (libsource (lib "eagle-import") (part "UCC27531"))
    )
    (comp (ref "U21")
      (value "UCC27531")
      (footprint "eagle-import:DBV_R-PDSO-G6")
      (libsource (lib "eagle-import") (part "UCC27531"))
    )
    (comp (ref "U22")
      (value "UCC27531")
      (footprint "eagle-import:DBV_R-PDSO-G6")
      (libsource (lib "eagle-import") (part "UCC27531"))
    )
    (comp (ref "U23")
      (value "UCC27531")
      (footprint "eagle-import:DBV_R-PDSO-G6")
      (libsource (lib "eagle-import") (part "UCC27531"))
    )
    (comp (ref "U24")
      (value "UCC27531")
      (footprint "eagle-import:DBV_R-PDSO-G6")
      (libsource (lib "eagle-import") (part "UCC27531"))
    )
    (comp (ref "U25")
      (value "UCC27531")
      (footprint "eagle-import:DBV_R-PDSO-G6")
      (libsource (lib "eagle-import") (part "UCC27531"))
    )
    (comp (ref "U26")
      (value "UCC27531")
      (footprint "eagle-import:DBV_R-PDSO-G6")
      (libsource (lib "eagle-import") (part "UCC27531"))
    )
    (comp (ref "U27")
      (value "UCC27531")
      (footprint "eagle-import:DBV_R-PDSO-G6")
      (libsource (lib "eagle-import") (part "UCC27531"))
    )
    (comp (ref "U28")
      (value "UCC27531")
      (footprint "eagle-import:DBV_R-PDSO-G6")
      (libsource (lib "eagle-import") (part "UCC27531"))
    )
    (comp (ref "U29")
      (value "UCC27531")
      (footprint "eagle-import:DBV_R-PDSO-G6")
      (libsource (lib "eagle-import") (part "UCC27531"))
    )
    (comp (ref "U30")
      (value "UCC27531")
      (footprint "eagle-import:DBV_R-PDSO-G6")
      (libsource (lib "eagle-import") (part "UCC27531"))
    )
    (comp (ref "U31")
      (value "UCC27531")
      (footprint "eagle-import:DBV_R-PDSO-G6")
      (libsource (lib "eagle-import") (part "UCC27531"))
    )
    (comp (ref "U32")
      (value "UCC27531")
      (footprint "eagle-import:DBV_R-PDSO-G6")
      (libsource (lib "eagle-import") (part "UCC27531"))
    )
    (comp (ref "U33")
      (value "UCC27531")
      (footprint "eagle-import:DBV_R-PDSO-G6")
      (libsource (lib "eagle-import") (part "UCC27531"))
    )
    (comp (ref "U34")
      (value "UCC27531")
      (footprint "eagle-import:DBV_R-PDSO-G6")
      (libsource (lib "eagle-import") (part "UCC27531"))
    )
    (comp (ref "U35")
      (value "UCC27531")
      (footprint "eagle-import:DBV_R-PDSO-G6")
      (libsource (lib "eagle-import") (part "UCC27531"))
    )
    (comp (ref "U36")
      (value "UCC27531")
      (footprint "eagle-import:DBV_R-PDSO-G6")
      (libsource (lib "eagle-import") (part "UCC27531"))
    )
    (comp (ref "U37")
      (value "UCC27531")
      (footprint "eagle-import:DBV_R-PDSO-G6")
      (libsource (lib "eagle-import") (part "UCC27531"))
    )
    (comp (ref "U38")
      (value "UCC27531")
      (footprint "eagle-import:DBV_R-PDSO-G6")
      (libsource (lib "eagle-import") (part "UCC27531"))
    )
    (comp (ref "U39")
      (value "UCC27531")
      (footprint "eagle-import:DBV_R-PDSO-G6")
      (libsource (lib "eagle-import") (part "UCC27531"))
    )
    (comp (ref "U40")
      (value "UCC27531")
      (footprint "eagle-import:DBV_R-PDSO-G6")
      (libsource (lib "eagle-import") (part "UCC27531"))
    )
    (comp (ref "U41")
      (value "UCC27531")
      (footprint "eagle-import:DBV_R-PDSO-G6")
      (libsource (lib "eagle-import") (part "UCC27531"))
    )
    (comp (ref "U42")
      (value "UCC27531")
      (footprint "eagle-import:DBV_R-PDSO-G6")
      (libsource (lib "eagle-import") (part "UCC27531"))
    )
    (comp (ref "U43")
      (value "UCC27531")
      (footprint "eagle-import:DBV_R-PDSO-G6")
      (libsource (lib "eagle-import") (part "UCC27531"))
    )
    (comp (ref "U44")
      (value "UCC27531")
      (footprint "eagle-import:DBV_R-PDSO-G6")
      (libsource (lib "eagle-import") (part "UCC27531"))
    )
    (comp (ref "U45")
      (value "UCC27531")
      (footprint "eagle-import:DBV_R-PDSO-G6")
      (libsource (lib "eagle-import") (part "UCC27531"))
    )
    (comp (ref "U46")
      (value "UCC27531")
      (footprint "eagle-import:DBV_R-PDSO-G6")
      (libsource (lib "eagle-import") (part "UCC27531"))
    )
    (comp (ref "U47")
      (value "UCC27531")
      (footprint "eagle-import:DBV_R-PDSO-G6")
      (libsource (lib "eagle-import") (part "UCC27531"))
    )
    (comp (ref "U48")
      (value "UCC27531")
      (footprint "eagle-import:DBV_R-PDSO-G6")
      (libsource (lib "eagle-import") (part "UCC27531"))
    )
    (comp (ref "U49")
      (value "UCC27531")
      (footprint "eagle-import:DBV_R-PDSO-G6")
      (libsource (lib "eagle-import") (part "UCC27531"))
    )
    (comp (ref "U50")
      (value "UCC27531")
      (footprint "eagle-import:DBV_R-PDSO-G6")
      (libsource (lib "eagle-import") (part "UCC27531"))
    )
    (comp (ref "U51")
      (value "UCC27531")
      (footprint "eagle-import:DBV_R-PDSO-G6")
      (libsource (lib "eagle-import") (part "UCC27531"))
    )
    (comp (ref "U52")
      (value "UCC27531")
      (footprint "eagle-import:DBV_R-PDSO-G6")
      (libsource (lib "eagle-import") (part "UCC27531"))
    )
    (comp (ref "U53")
      (value "UCC27531")
      (footprint "eagle-import:DBV_R-PDSO-G6")
      (libsource (lib "eagle-import") (part "UCC27531"))
    )
    (comp (ref "U54")
      (value "UCC27531")
      (footprint "eagle-import:DBV_R-PDSO-G6")
      (libsource (lib "eagle-import") (part "UCC27531"))
    )
    (comp (ref "U55")
      (value "UCC27531")
      (footprint "eagle-import:DBV_R-PDSO-G6")
      (libsource (lib "eagle-import") (part "UCC27531"))
    )
    (comp (ref "U56")
      (value "UCC27531")
      (footprint "eagle-import:DBV_R-PDSO-G6")
      (libsource (lib "eagle-import") (part "UCC27531"))
    )
    (comp (ref "U57")
      (value "UCC27531")
      (footprint "eagle-import:DBV_R-PDSO-G6")
      (libsource (lib "eagle-import") (part "UCC27531"))
    )
    (comp (ref "U58")
      (value "UCC27531")
      (footprint "eagle-import:DBV_R-PDSO-G6")
      (libsource (lib "eagle-import") (part "UCC27531"))
    )
    (comp (ref "U59")
      (value "UCC27531")
      (footprint "eagle-import:DBV_R-PDSO-G6")
      (libsource (lib "eagle-import") (part "UCC27531"))
    )
    (comp (ref "U60")
      (value "UCC27531")
      (footprint "eagle-import:DBV_R-PDSO-G6")
      (libsource (lib "eagle-import") (part "UCC27531"))
    )
    (comp (ref "U61")
      (value "UCC27531")
      (footprint "eagle-import:DBV_R-PDSO-G6")
      (libsource (lib "eagle-import") (part "UCC27531"))
    )
    (comp (ref "U62")
      (value "UCC27531")
      (footprint "eagle-import:DBV_R-PDSO-G6")
      (libsource (lib "eagle-import") (part "UCC27531"))
    )
    (comp (ref "U63")
      (value "UCC27531")
      (footprint "eagle-import:DBV_R-PDSO-G6")
      (libsource (lib "eagle-import") (part "UCC27531"))
    )
    (comp (ref "U64")
      (value "UCC27531")
      (footprint "eagle-import:DBV_R-PDSO-G6")
      (libsource (lib "eagle-import") (part "UCC27531"))
    )
    (comp (ref "U65")
      (value "LTC4365")
      (footprint "eagle-import:TSOT23-8")
      (libsource (lib "eagle-import") (part "LTC4365"))
    )
    (comp (ref "U66")
      (value "FT232R")
      (footprint "eagle-import:SSOP28")
      (libsource (lib "eagle-import") (part "FT232R"))
    )
    (comp (ref "X1")
      (value "MINI-USB")
      (footprint "eagle-import:32005-201")
      (libsource (lib "eagle-import") (part "MINI_USB"))
    )
    (comp (ref "X2")
      (value "BNC")
      (footprint "eagle-import:BNC_CUSTOM")
      (libsource (lib "eagle-import") (part "BNC"))
    )
  )
  (nets
    (net (code "1") (name "/3V3") (class "Default")
      (node (ref "C137") (pin "1") (pinfunction "1_1") (pintype "passive"))
      (node (ref "LED1") (pin "A") (pinfunction "A_A") (pintype "passive"))
      (node (ref "LED2") (pin "A") (pinfunction "A_A") (pintype "passive"))
      (node (ref "U66") (pin "17") (pinfunction "3V3OUT_17") (pintype "power_in"))
      (node (ref "U66") (pin "4") (pinfunction "VCCIO_4") (pintype "power_in"))
    )
    (net (code "2") (name "/BNC") (class "Default")
      (node (ref "JP2") (pin "39") (pinfunction "39_39") (pintype "passive"))
      (node (ref "X2") (pin "1") (pinfunction "1_1") (pintype "passive"))
    )
    (net (code "3") (name "/D+") (class "Default")
      (node (ref "U66") (pin "15") (pinfunction "USBDP_15") (pintype "bidirectional"))
      (node (ref "X1") (pin "3") (pinfunction "3_3") (pintype "passive"))
    )
    (net (code "4") (name "/D-") (class "Default")
      (node (ref "U66") (pin "16") (pinfunction "USBDM_16") (pintype "bidirectional"))
      (node (ref "X1") (pin "2") (pinfunction "2_2") (pintype "passive"))
    )
    (net (code "5") (name "/ENABLE") (class "Default")
      (node (ref "JUMPER") (pin "2") (pinfunction "2_2") (pintype "passive"))
      (node (ref "U1") (pin "1") (pinfunction "EN_1") (pintype "input"))
      (node (ref "U10") (pin "1") (pinfunction "EN_1") (pintype "input"))
      (node (ref "U11") (pin "1") (pinfunction "EN_1") (pintype "input"))
      (node (ref "U12") (pin "1") (pinfunction "EN_1") (pintype "input"))
      (node (ref "U13") (pin "1") (pinfunction "EN_1") (pintype "input"))
      (node (ref "U14") (pin "1") (pinfunction "EN_1") (pintype "input"))
      (node (ref "U15") (pin "1") (pinfunction "EN_1") (pintype "input"))
      (node (ref "U16") (pin "1") (pinfunction "EN_1") (pintype "input"))
      (node (ref "U17") (pin "1") (pinfunction "EN_1") (pintype "input"))
      (node (ref "U18") (pin "1") (pinfunction "EN_1") (pintype "input"))
      (node (ref "U19") (pin "1") (pinfunction "EN_1") (pintype "input"))
      (node (ref "U2") (pin "1") (pinfunction "EN_1") (pintype "input"))
      (node (ref "U20") (pin "1") (pinfunction "EN_1") (pintype "input"))
      (node (ref "U21") (pin "1") (pinfunction "EN_1") (pintype "input"))
      (node (ref "U22") (pin "1") (pinfunction "EN_1") (pintype "input"))
      (node (ref "U23") (pin "1") (pinfunction "EN_1") (pintype "input"))
      (node (ref "U24") (pin "1") (pinfunction "EN_1") (pintype "input"))
      (node (ref "U25") (pin "1") (pinfunction "EN_1") (pintype "input"))
      (node (ref "U26") (pin "1") (pinfunction "EN_1") (pintype "input"))
      (node (ref "U27") (pin "1") (pinfunction "EN_1") (pintype "input"))
      (node (ref "U28") (pin "1") (pinfunction "EN_1") (pintype "input"))
      (node (ref "U29") (pin "1") (pinfunction "EN_1") (pintype "input"))
      (node (ref "U3") (pin "1") (pinfunction "EN_1") (pintype "input"))
      (node (ref "U30") (pin "1") (pinfunction "EN_1") (pintype "input"))
      (node (ref "U31") (pin "1") (pinfunction "EN_1") (pintype "input"))
      (node (ref "U32") (pin "1") (pinfunction "EN_1") (pintype "input"))
      (node (ref "U33") (pin "1") (pinfunction "EN_1") (pintype "input"))
      (node (ref "U34") (pin "1") (pinfunction "EN_1") (pintype "input"))
      (node (ref "U35") (pin "1") (pinfunction "EN_1") (pintype "input"))
      (node (ref "U36") (pin "1") (pinfunction "EN_1") (pintype "input"))
      (node (ref "U37") (pin "1") (pinfunction "EN_1") (pintype "input"))
      (node (ref "U38") (pin "1") (pinfunction "EN_1") (pintype "input"))
      (node (ref "U39") (pin "1") (pinfunction "EN_1") (pintype "input"))
      (node (ref "U4") (pin "1") (pinfunction "EN_1") (pintype "input"))
      (node (ref "U40") (pin "1") (pinfunction "EN_1") (pintype "input"))
      (node (ref "U41") (pin "1") (pinfunction "EN_1") (pintype "input"))
      (node (ref "U42") (pin "1") (pinfunction "EN_1") (pintype "input"))
      (node (ref "U43") (pin "1") (pinfunction "EN_1") (pintype "input"))
      (node (ref "U44") (pin "1") (pinfunction "EN_1") (pintype "input"))
      (node (ref "U45") (pin "1") (pinfunction "EN_1") (pintype "input"))
      (node (ref "U46") (pin "1") (pinfunction "EN_1") (pintype "input"))
      (node (ref "U47") (pin "1") (pinfunction "EN_1") (pintype "input"))
      (node (ref "U48") (pin "1") (pinfunction "EN_1") (pintype "input"))
      (node (ref "U49") (pin "1") (pinfunction "EN_1") (pintype "input"))
      (node (ref "U5") (pin "1") (pinfunction "EN_1") (pintype "input"))
      (node (ref "U50") (pin "1") (pinfunction "EN_1") (pintype "input"))
      (node (ref "U51") (pin "1") (pinfunction "EN_1") (pintype "input"))
      (node (ref "U52") (pin "1") (pinfunction "EN_1") (pintype "input"))
      (node (ref "U53") (pin "1") (pinfunction "EN_1") (pintype "input"))
      (node (ref "U54") (pin "1") (pinfunction "EN_1") (pintype "input"))
      (node (ref "U55") (pin "1") (pinfunction "EN_1") (pintype "input"))
      (node (ref "U56") (pin "1") (pinfunction "EN_1") (pintype "input"))
      (node (ref "U57") (pin "1") (pinfunction "EN_1") (pintype "input"))
      (node (ref "U58") (pin "1") (pinfunction "EN_1") (pintype "input"))
      (node (ref "U59") (pin "1") (pinfunction "EN_1") (pintype "input"))
      (node (ref "U6") (pin "1") (pinfunction "EN_1") (pintype "input"))
      (node (ref "U60") (pin "1") (pinfunction "EN_1") (pintype "input"))
      (node (ref "U61") (pin "1") (pinfunction "EN_1") (pintype "input"))
      (node (ref "U62") (pin "1") (pinfunction "EN_1") (pintype "input"))
      (node (ref "U63") (pin "1") (pinfunction "EN_1") (pintype "input"))
      (node (ref "U64") (pin "1") (pinfunction "EN_1") (pintype "input"))
      (node (ref "U7") (pin "1") (pinfunction "EN_1") (pintype "input"))
      (node (ref "U8") (pin "1") (pinfunction "EN_1") (pintype "input"))
      (node (ref "U9") (pin "1") (pinfunction "EN_1") (pintype "input"))
    )
    (net (code "6") (name "/FPGA-EN") (class "Default")
      (node (ref "JP2") (pin "37") (pinfunction "37_37") (pintype "passive"))
      (node (ref "JUMPER") (pin "3") (pinfunction "3_3") (pintype "passive"))
    )
    (net (code "7") (name "/ID") (class "Default")
      (node (ref "X1") (pin "4") (pinfunction "4_4") (pintype "passive"))
    )
    (net (code "8") (name "/IN0") (class "Default")
      (node (ref "JP1") (pin "1") (pinfunction "1_1") (pintype "passive"))
      (node (ref "U1") (pin "2") (pinfunction "IN_2") (pintype "input"))
    )
    (net (code "9") (name "/IN1") (class "Default")
      (node (ref "JP1") (pin "3") (pinfunction "3_3") (pintype "passive"))
      (node (ref "U2") (pin "2") (pinfunction "IN_2") (pintype "input"))
    )
    (net (code "10") (name "/IN2") (class "Default")
      (node (ref "JP1") (pin "5") (pinfunction "5_5") (pintype "passive"))
      (node (ref "U3") (pin "2") (pinfunction "IN_2") (pintype "input"))
    )
    (net (code "11") (name "/IN3") (class "Default")
      (node (ref "JP1") (pin "7") (pinfunction "7_7") (pintype "passive"))
      (node (ref "U4") (pin "2") (pinfunction "IN_2") (pintype "input"))
    )
    (net (code "12") (name "/IN4") (class "Default")
      (node (ref "JP1") (pin "9") (pinfunction "9_9") (pintype "passive"))
      (node (ref "U5") (pin "2") (pinfunction "IN_2") (pintype "input"))
    )
    (net (code "13") (name "/IN5") (class "Default")
      (node (ref "JP1") (pin "13") (pinfunction "13_13") (pintype "passive"))
      (node (ref "U6") (pin "2") (pinfunction "IN_2") (pintype "input"))
    )
    (net (code "14") (name "/IN6") (class "Default")
      (node (ref "JP1") (pin "15") (pinfunction "15_15") (pintype "passive"))
      (node (ref "U7") (pin "2") (pinfunction "IN_2") (pintype "input"))
    )
    (net (code "15") (name "/IN7") (class "Default")
      (node (ref "JP1") (pin "17") (pinfunction "17_17") (pintype "passive"))
      (node (ref "U8") (pin "2") (pinfunction "IN_2") (pintype "input"))
    )
    (net (code "16") (name "/IN8") (class "Default")
      (node (ref "JP1") (pin "19") (pinfunction "19_19") (pintype "passive"))
      (node (ref "U9") (pin "2") (pinfunction "IN_2") (pintype "input"))
    )
    (net (code "17") (name "/IN9") (class "Default")
      (node (ref "JP1") (pin "21") (pinfunction "21_21") (pintype "passive"))
      (node (ref "U10") (pin "2") (pinfunction "IN_2") (pintype "input"))
    )
    (net (code "18") (name "/IN10") (class "Default")
      (node (ref "JP1") (pin "23") (pinfunction "23_23") (pintype "passive"))
      (node (ref "U11") (pin "2") (pinfunction "IN_2") (pintype "input"))
    )
    (net (code "19") (name "/IN11") (class "Default")
      (node (ref "JP1") (pin "25") (pinfunction "25_25") (pintype "passive"))
      (node (ref "U12") (pin "2") (pinfunction "IN_2") (pintype "input"))
    )
    (net (code "20") (name "/IN12") (class "Default")
      (node (ref "JP1") (pin "27") (pinfunction "27_27") (pintype "passive"))
      (node (ref "U13") (pin "2") (pinfunction "IN_2") (pintype "input"))
    )
    (net (code "21") (name "/IN13") (class "Default")
      (node (ref "JP1") (pin "31") (pinfunction "31_31") (pintype "passive"))
      (node (ref "U14") (pin "2") (pinfunction "IN_2") (pintype "input"))
    )
    (net (code "22") (name "/IN14") (class "Default")
      (node (ref "JP1") (pin "33") (pinfunction "33_33") (pintype "passive"))
      (node (ref "U15") (pin "2") (pinfunction "IN_2") (pintype "input"))
    )
    (net (code "23") (name "/IN15") (class "Default")
      (node (ref "JP1") (pin "35") (pinfunction "35_35") (pintype "passive"))
      (node (ref "U16") (pin "2") (pinfunction "IN_2") (pintype "input"))
    )
    (net (code "24") (name "/IN16") (class "Default")
      (node (ref "JP1") (pin "40") (pinfunction "40_40") (pintype "passive"))
      (node (ref "U17") (pin "2") (pinfunction "IN_2") (pintype "input"))
    )
    (net (code "25") (name "/IN17") (class "Default")
      (node (ref "JP1") (pin "38") (pinfunction "38_38") (pintype "passive"))
      (node (ref "U18") (pin "2") (pinfunction "IN_2") (pintype "input"))
    )
    (net (code "26") (name "/IN18") (class "Default")
      (node (ref "JP1") (pin "36") (pinfunction "36_36") (pintype "passive"))
      (node (ref "U19") (pin "2") (pinfunction "IN_2") (pintype "input"))
    )
    (net (code "27") (name "/IN19") (class "Default")
      (node (ref "JP1") (pin "34") (pinfunction "34_34") (pintype "passive"))
      (node (ref "U20") (pin "2") (pinfunction "IN_2") (pintype "input"))
    )
    (net (code "28") (name "/IN20") (class "Default")
      (node (ref "JP1") (pin "32") (pinfunction "32_32") (pintype "passive"))
      (node (ref "U21") (pin "2") (pinfunction "IN_2") (pintype "input"))
    )
    (net (code "29") (name "/IN21") (class "Default")
      (node (ref "JP1") (pin "28") (pinfunction "28_28") (pintype "passive"))
      (node (ref "U22") (pin "2") (pinfunction "IN_2") (pintype "input"))
    )
    (net (code "30") (name "/IN22") (class "Default")
      (node (ref "JP1") (pin "26") (pinfunction "26_26") (pintype "passive"))
      (node (ref "U23") (pin "2") (pinfunction "IN_2") (pintype "input"))
    )
    (net (code "31") (name "/IN23") (class "Default")
      (node (ref "JP1") (pin "24") (pinfunction "24_24") (pintype "passive"))
      (node (ref "U24") (pin "2") (pinfunction "IN_2") (pintype "input"))
    )
    (net (code "32") (name "/IN24") (class "Default")
      (node (ref "JP1") (pin "22") (pinfunction "22_22") (pintype "passive"))
      (node (ref "U25") (pin "2") (pinfunction "IN_2") (pintype "input"))
    )
    (net (code "33") (name "/IN25") (class "Default")
      (node (ref "JP1") (pin "20") (pinfunction "20_20") (pintype "passive"))
      (node (ref "U26") (pin "2") (pinfunction "IN_2") (pintype "input"))
    )
    (net (code "34") (name "/IN26") (class "Default")
      (node (ref "JP1") (pin "18") (pinfunction "18_18") (pintype "passive"))
      (node (ref "U27") (pin "2") (pinfunction "IN_2") (pintype "input"))
    )
    (net (code "35") (name "/IN27") (class "Default")
      (node (ref "JP1") (pin "16") (pinfunction "16_16") (pintype "passive"))
      (node (ref "U28") (pin "2") (pinfunction "IN_2") (pintype "input"))
    )
    (net (code "36") (name "/IN28") (class "Default")
      (node (ref "JP1") (pin "14") (pinfunction "14_14") (pintype "passive"))
      (node (ref "U29") (pin "2") (pinfunction "IN_2") (pintype "input"))
    )
    (net (code "37") (name "/IN29") (class "Default")
      (node (ref "JP1") (pin "10") (pinfunction "10_10") (pintype "passive"))
      (node (ref "U30") (pin "2") (pinfunction "IN_2") (pintype "input"))
    )
    (net (code "38") (name "/IN30") (class "Default")
      (node (ref "JP1") (pin "8") (pinfunction "8_8") (pintype "passive"))
      (node (ref "U31") (pin "2") (pinfunction "IN_2") (pintype "input"))
    )
    (net (code "39") (name "/IN31") (class "Default")
      (node (ref "JP1") (pin "6") (pinfunction "6_6") (pintype "passive"))
      (node (ref "U32") (pin "2") (pinfunction "IN_2") (pintype "input"))
    )
    (net (code "40") (name "/IN32") (class "Default")
      (node (ref "JP2") (pin "1") (pinfunction "1_1") (pintype "passive"))
      (node (ref "U33") (pin "2") (pinfunction "IN_2") (pintype "input"))
    )
    (net (code "41") (name "/IN33") (class "Default")
      (node (ref "JP2") (pin "3") (pinfunction "3_3") (pintype "passive"))
      (node (ref "U34") (pin "2") (pinfunction "IN_2") (pintype "input"))
    )
    (net (code "42") (name "/IN34") (class "Default")
      (node (ref "JP2") (pin "5") (pinfunction "5_5") (pintype "passive"))
      (node (ref "U35") (pin "2") (pinfunction "IN_2") (pintype "input"))
    )
    (net (code "43") (name "/IN35") (class "Default")
      (node (ref "JP2") (pin "7") (pinfunction "7_7") (pintype "passive"))
      (node (ref "U36") (pin "2") (pinfunction "IN_2") (pintype "input"))
    )
    (net (code "44") (name "/IN36") (class "Default")
      (node (ref "JP2") (pin "9") (pinfunction "9_9") (pintype "passive"))
      (node (ref "U37") (pin "2") (pinfunction "IN_2") (pintype "input"))
    )
    (net (code "45") (name "/IN37") (class "Default")
      (node (ref "JP2") (pin "13") (pinfunction "13_13") (pintype "passive"))
      (node (ref "U38") (pin "2") (pinfunction "IN_2") (pintype "input"))
    )
    (net (code "46") (name "/IN38") (class "Default")
      (node (ref "JP2") (pin "15") (pinfunction "15_15") (pintype "passive"))
      (node (ref "U39") (pin "2") (pinfunction "IN_2") (pintype "input"))
    )
    (net (code "47") (name "/IN39") (class "Default")
      (node (ref "JP2") (pin "17") (pinfunction "17_17") (pintype "passive"))
      (node (ref "U40") (pin "2") (pinfunction "IN_2") (pintype "input"))
    )
    (net (code "48") (name "/IN40") (class "Default")
      (node (ref "JP2") (pin "19") (pinfunction "19_19") (pintype "passive"))
      (node (ref "U41") (pin "2") (pinfunction "IN_2") (pintype "input"))
    )
    (net (code "49") (name "/IN41") (class "Default")
      (node (ref "JP2") (pin "21") (pinfunction "21_21") (pintype "passive"))
      (node (ref "U42") (pin "2") (pinfunction "IN_2") (pintype "input"))
    )
    (net (code "50") (name "/IN42") (class "Default")
      (node (ref "JP2") (pin "23") (pinfunction "23_23") (pintype "passive"))
      (node (ref "U43") (pin "2") (pinfunction "IN_2") (pintype "input"))
    )
    (net (code "51") (name "/IN43") (class "Default")
      (node (ref "JP2") (pin "25") (pinfunction "25_25") (pintype "passive"))
      (node (ref "U44") (pin "2") (pinfunction "IN_2") (pintype "input"))
    )
    (net (code "52") (name "/IN44") (class "Default")
      (node (ref "JP2") (pin "27") (pinfunction "27_27") (pintype "passive"))
      (node (ref "U45") (pin "2") (pinfunction "IN_2") (pintype "input"))
    )
    (net (code "53") (name "/IN45") (class "Default")
      (node (ref "JP2") (pin "31") (pinfunction "31_31") (pintype "passive"))
      (node (ref "U46") (pin "2") (pinfunction "IN_2") (pintype "input"))
    )
    (net (code "54") (name "/IN46") (class "Default")
      (node (ref "JP2") (pin "33") (pinfunction "33_33") (pintype "passive"))
      (node (ref "U47") (pin "2") (pinfunction "IN_2") (pintype "input"))
    )
    (net (code "55") (name "/IN47") (class "Default")
      (node (ref "JP2") (pin "35") (pinfunction "35_35") (pintype "passive"))
      (node (ref "U48") (pin "2") (pinfunction "IN_2") (pintype "input"))
    )
    (net (code "56") (name "/IN48") (class "Default")
      (node (ref "JP2") (pin "40") (pinfunction "40_40") (pintype "passive"))
      (node (ref "U49") (pin "2") (pinfunction "IN_2") (pintype "input"))
    )
    (net (code "57") (name "/IN49") (class "Default")
      (node (ref "JP2") (pin "38") (pinfunction "38_38") (pintype "passive"))
      (node (ref "U50") (pin "2") (pinfunction "IN_2") (pintype "input"))
    )
    (net (code "58") (name "/IN50") (class "Default")
      (node (ref "JP2") (pin "36") (pinfunction "36_36") (pintype "passive"))
      (node (ref "U51") (pin "2") (pinfunction "IN_2") (pintype "input"))
    )
    (net (code "59") (name "/IN51") (class "Default")
      (node (ref "JP2") (pin "34") (pinfunction "34_34") (pintype "passive"))
      (node (ref "U52") (pin "2") (pinfunction "IN_2") (pintype "input"))
    )
    (net (code "60") (name "/IN52") (class "Default")
      (node (ref "JP2") (pin "32") (pinfunction "32_32") (pintype "passive"))
      (node (ref "U53") (pin "2") (pinfunction "IN_2") (pintype "input"))
    )
    (net (code "61") (name "/IN53") (class "Default")
      (node (ref "JP2") (pin "28") (pinfunction "28_28") (pintype "passive"))
      (node (ref "U54") (pin "2") (pinfunction "IN_2") (pintype "input"))
    )
    (net (code "62") (name "/IN54") (class "Default")
      (node (ref "JP2") (pin "26") (pinfunction "26_26") (pintype "passive"))
      (node (ref "U55") (pin "2") (pinfunction "IN_2") (pintype "input"))
    )
    (net (code "63") (name "/IN55") (class "Default")
      (node (ref "JP2") (pin "24") (pinfunction "24_24") (pintype "passive"))
      (node (ref "U56") (pin "2") (pinfunction "IN_2") (pintype "input"))
    )
    (net (code "64") (name "/IN56") (class "Default")
      (node (ref "JP2") (pin "22") (pinfunction "22_22") (pintype "passive"))
      (node (ref "U57") (pin "2") (pinfunction "IN_2") (pintype "input"))
    )
    (net (code "65") (name "/IN57") (class "Default")
      (node (ref "JP2") (pin "20") (pinfunction "20_20") (pintype "passive"))
      (node (ref "U58") (pin "2") (pinfunction "IN_2") (pintype "input"))
    )
    (net (code "66") (name "/IN58") (class "Default")
      (node (ref "JP2") (pin "18") (pinfunction "18_18") (pintype "passive"))
      (node (ref "U59") (pin "2") (pinfunction "IN_2") (pintype "input"))
    )
    (net (code "67") (name "/IN59") (class "Default")
      (node (ref "JP2") (pin "16") (pinfunction "16_16") (pintype "passive"))
      (node (ref "U60") (pin "2") (pinfunction "IN_2") (pintype "input"))
    )
    (net (code "68") (name "/IN60") (class "Default")
      (node (ref "JP2") (pin "14") (pinfunction "14_14") (pintype "passive"))
      (node (ref "U61") (pin "2") (pinfunction "IN_2") (pintype "input"))
    )
    (net (code "69") (name "/IN61") (class "Default")
      (node (ref "JP2") (pin "10") (pinfunction "10_10") (pintype "passive"))
      (node (ref "U62") (pin "2") (pinfunction "IN_2") (pintype "input"))
    )
    (net (code "70") (name "/IN62") (class "Default")
      (node (ref "JP2") (pin "8") (pinfunction "8_8") (pintype "passive"))
      (node (ref "U63") (pin "2") (pinfunction "IN_2") (pintype "input"))
    )
    (net (code "71") (name "/IN63") (class "Default")
      (node (ref "JP2") (pin "6") (pinfunction "6_6") (pintype "passive"))
      (node (ref "U64") (pin "2") (pinfunction "IN_2") (pintype "input"))
    )
    (net (code "73") (name "/OSCI") (class "Default")
      (node (ref "C141") (pin "1") (pinfunction "1_1") (pintype "passive"))
      (node (ref "Q1") (pin "1") (pinfunction "1_1") (pintype "passive"))
      (node (ref "U66") (pin "27") (pinfunction "OSCI_27") (pintype "bidirectional"))
    )
    (net (code "74") (name "/OSCO") (class "Default")
      (node (ref "C140") (pin "1") (pinfunction "1_1") (pintype "passive"))
      (node (ref "Q1") (pin "2") (pinfunction "2_2") (pintype "passive"))
      (node (ref "U66") (pin "28") (pinfunction "OSCO_28") (pintype "bidirectional"))
    )
    (net (code "75") (name "/OUT0") (class "Default")
      (node (ref "C65") (pin "2") (pinfunction "2_2") (pintype "passive"))
      (node (ref "SV1") (pin "1") (pinfunction "1_1") (pintype "passive"))
    )
    (net (code "76") (name "/OUT1") (class "Default")
      (node (ref "C66") (pin "2") (pinfunction "2_2") (pintype "passive"))
      (node (ref "SV1") (pin "3") (pinfunction "3_3") (pintype "passive"))
    )
    (net (code "77") (name "/OUT2") (class "Default")
      (node (ref "C67") (pin "2") (pinfunction "2_2") (pintype "passive"))
      (node (ref "SV1") (pin "5") (pinfunction "5_5") (pintype "passive"))
    )
    (net (code "78") (name "/OUT3") (class "Default")
      (node (ref "C68") (pin "2") (pinfunction "2_2") (pintype "passive"))
      (node (ref "SV1") (pin "7") (pinfunction "7_7") (pintype "passive"))
    )
    (net (code "79") (name "/OUT4") (class "Default")
      (node (ref "C69") (pin "2") (pinfunction "2_2") (pintype "passive"))
      (node (ref "SV1") (pin "9") (pinfunction "9_9") (pintype "passive"))
    )
    (net (code "80") (name "/OUT5") (class "Default")
      (node (ref "C70") (pin "2") (pinfunction "2_2") (pintype "passive"))
      (node (ref "SV1") (pin "11") (pinfunction "11_11") (pintype "passive"))
    )
    (net (code "81") (name "/OUT6") (class "Default")
      (node (ref "C71") (pin "2") (pinfunction "2_2") (pintype "passive"))
      (node (ref "SV1") (pin "13") (pinfunction "13_13") (pintype "passive"))
    )
    (net (code "82") (name "/OUT7") (class "Default")
      (node (ref "C72") (pin "2") (pinfunction "2_2") (pintype "passive"))
      (node (ref "SV1") (pin "15") (pinfunction "15_15") (pintype "passive"))
    )
    (net (code "83") (name "/OUT8") (class "Default")
      (node (ref "C73") (pin "2") (pinfunction "2_2") (pintype "passive"))
      (node (ref "SV1") (pin "17") (pinfunction "17_17") (pintype "passive"))
    )
    (net (code "84") (name "/OUT9") (class "Default")
      (node (ref "C74") (pin "2") (pinfunction "2_2") (pintype "passive"))
      (node (ref "SV1") (pin "19") (pinfunction "19_19") (pintype "passive"))
    )
    (net (code "85") (name "/OUT10") (class "Default")
      (node (ref "C75") (pin "2") (pinfunction "2_2") (pintype "passive"))
      (node (ref "SV1") (pin "21") (pinfunction "21_21") (pintype "passive"))
    )
    (net (code "86") (name "/OUT11") (class "Default")
      (node (ref "C76") (pin "2") (pinfunction "2_2") (pintype "passive"))
      (node (ref "SV1") (pin "23") (pinfunction "23_23") (pintype "passive"))
    )
    (net (code "87") (name "/OUT12") (class "Default")
      (node (ref "C77") (pin "2") (pinfunction "2_2") (pintype "passive"))
      (node (ref "SV1") (pin "25") (pinfunction "25_25") (pintype "passive"))
    )
    (net (code "88") (name "/OUT13") (class "Default")
      (node (ref "C78") (pin "2") (pinfunction "2_2") (pintype "passive"))
      (node (ref "SV1") (pin "27") (pinfunction "27_27") (pintype "passive"))
    )
    (net (code "89") (name "/OUT14") (class "Default")
      (node (ref "C79") (pin "2") (pinfunction "2_2") (pintype "passive"))
      (node (ref "SV1") (pin "29") (pinfunction "29_29") (pintype "passive"))
    )
    (net (code "90") (name "/OUT15") (class "Default")
      (node (ref "C80") (pin "2") (pinfunction "2_2") (pintype "passive"))
      (node (ref "SV1") (pin "31") (pinfunction "31_31") (pintype "passive"))
    )
    (net (code "91") (name "/OUT16") (class "Default")
      (node (ref "C81") (pin "2") (pinfunction "2_2") (pintype "passive"))
      (node (ref "SV2") (pin "1") (pinfunction "1_1") (pintype "passive"))
    )
    (net (code "92") (name "/OUT17") (class "Default")
      (node (ref "C82") (pin "2") (pinfunction "2_2") (pintype "passive"))
      (node (ref "SV2") (pin "3") (pinfunction "3_3") (pintype "passive"))
    )
    (net (code "93") (name "/OUT18") (class "Default")
      (node (ref "C83") (pin "2") (pinfunction "2_2") (pintype "passive"))
      (node (ref "SV2") (pin "5") (pinfunction "5_5") (pintype "passive"))
    )
    (net (code "94") (name "/OUT19") (class "Default")
      (node (ref "C84") (pin "2") (pinfunction "2_2") (pintype "passive"))
      (node (ref "SV2") (pin "7") (pinfunction "7_7") (pintype "passive"))
    )
    (net (code "95") (name "/OUT20") (class "Default")
      (node (ref "C85") (pin "2") (pinfunction "2_2") (pintype "passive"))
      (node (ref "SV2") (pin "9") (pinfunction "9_9") (pintype "passive"))
    )
    (net (code "96") (name "/OUT21") (class "Default")
      (node (ref "C86") (pin "2") (pinfunction "2_2") (pintype "passive"))
      (node (ref "SV2") (pin "11") (pinfunction "11_11") (pintype "passive"))
    )
    (net (code "97") (name "/OUT22") (class "Default")
      (node (ref "C87") (pin "2") (pinfunction "2_2") (pintype "passive"))
      (node (ref "SV2") (pin "13") (pinfunction "13_13") (pintype "passive"))
    )
    (net (code "98") (name "/OUT23") (class "Default")
      (node (ref "C88") (pin "2") (pinfunction "2_2") (pintype "passive"))
      (node (ref "SV2") (pin "15") (pinfunction "15_15") (pintype "passive"))
    )
    (net (code "99") (name "/OUT24") (class "Default")
      (node (ref "C89") (pin "2") (pinfunction "2_2") (pintype "passive"))
      (node (ref "SV2") (pin "17") (pinfunction "17_17") (pintype "passive"))
    )
    (net (code "100") (name "/OUT25") (class "Default")
      (node (ref "C90") (pin "2") (pinfunction "2_2") (pintype "passive"))
      (node (ref "SV2") (pin "19") (pinfunction "19_19") (pintype "passive"))
    )
    (net (code "101") (name "/OUT26") (class "Default")
      (node (ref "C91") (pin "2") (pinfunction "2_2") (pintype "passive"))
      (node (ref "SV2") (pin "21") (pinfunction "21_21") (pintype "passive"))
    )
    (net (code "102") (name "/OUT27") (class "Default")
      (node (ref "C92") (pin "2") (pinfunction "2_2") (pintype "passive"))
      (node (ref "SV2") (pin "23") (pinfunction "23_23") (pintype "passive"))
    )
    (net (code "103") (name "/OUT28") (class "Default")
      (node (ref "C93") (pin "2") (pinfunction "2_2") (pintype "passive"))
      (node (ref "SV2") (pin "25") (pinfunction "25_25") (pintype "passive"))
    )
    (net (code "104") (name "/OUT29") (class "Default")
      (node (ref "C94") (pin "2") (pinfunction "2_2") (pintype "passive"))
      (node (ref "SV2") (pin "27") (pinfunction "27_27") (pintype "passive"))
    )
    (net (code "105") (name "/OUT30") (class "Default")
      (node (ref "C95") (pin "2") (pinfunction "2_2") (pintype "passive"))
      (node (ref "SV2") (pin "29") (pinfunction "29_29") (pintype "passive"))
    )
    (net (code "106") (name "/OUT31") (class "Default")
      (node (ref "C96") (pin "2") (pinfunction "2_2") (pintype "passive"))
      (node (ref "SV2") (pin "31") (pinfunction "31_31") (pintype "passive"))
    )
    (net (code "107") (name "/OUT32") (class "Default")
      (node (ref "C97") (pin "2") (pinfunction "2_2") (pintype "passive"))
      (node (ref "SV3") (pin "1") (pinfunction "1_1") (pintype "passive"))
    )
    (net (code "108") (name "/OUT33") (class "Default")
      (node (ref "C98") (pin "2") (pinfunction "2_2") (pintype "passive"))
      (node (ref "SV3") (pin "3") (pinfunction "3_3") (pintype "passive"))
    )
    (net (code "109") (name "/OUT34") (class "Default")
      (node (ref "C99") (pin "2") (pinfunction "2_2") (pintype "passive"))
      (node (ref "SV3") (pin "5") (pinfunction "5_5") (pintype "passive"))
    )
    (net (code "110") (name "/OUT35") (class "Default")
      (node (ref "C100") (pin "2") (pinfunction "2_2") (pintype "passive"))
      (node (ref "SV3") (pin "7") (pinfunction "7_7") (pintype "passive"))
    )
    (net (code "111") (name "/OUT36") (class "Default")
      (node (ref "C101") (pin "2") (pinfunction "2_2") (pintype "passive"))
      (node (ref "SV3") (pin "9") (pinfunction "9_9") (pintype "passive"))
    )
    (net (code "112") (name "/OUT37") (class "Default")
      (node (ref "C102") (pin "2") (pinfunction "2_2") (pintype "passive"))
      (node (ref "SV3") (pin "11") (pinfunction "11_11") (pintype "passive"))
    )
    (net (code "113") (name "/OUT38") (class "Default")
      (node (ref "C103") (pin "2") (pinfunction "2_2") (pintype "passive"))
      (node (ref "SV3") (pin "13") (pinfunction "13_13") (pintype "passive"))
    )
    (net (code "114") (name "/OUT39") (class "Default")
      (node (ref "C104") (pin "2") (pinfunction "2_2") (pintype "passive"))
      (node (ref "SV3") (pin "15") (pinfunction "15_15") (pintype "passive"))
    )
    (net (code "115") (name "/OUT40") (class "Default")
      (node (ref "C105") (pin "2") (pinfunction "2_2") (pintype "passive"))
      (node (ref "SV3") (pin "17") (pinfunction "17_17") (pintype "passive"))
    )
    (net (code "116") (name "/OUT41") (class "Default")
      (node (ref "C106") (pin "2") (pinfunction "2_2") (pintype "passive"))
      (node (ref "SV3") (pin "19") (pinfunction "19_19") (pintype "passive"))
    )
    (net (code "117") (name "/OUT42") (class "Default")
      (node (ref "C107") (pin "2") (pinfunction "2_2") (pintype "passive"))
      (node (ref "SV3") (pin "21") (pinfunction "21_21") (pintype "passive"))
    )
    (net (code "118") (name "/OUT43") (class "Default")
      (node (ref "C108") (pin "2") (pinfunction "2_2") (pintype "passive"))
      (node (ref "SV3") (pin "23") (pinfunction "23_23") (pintype "passive"))
    )
    (net (code "119") (name "/OUT44") (class "Default")
      (node (ref "C109") (pin "2") (pinfunction "2_2") (pintype "passive"))
      (node (ref "SV3") (pin "25") (pinfunction "25_25") (pintype "passive"))
    )
    (net (code "120") (name "/OUT45") (class "Default")
      (node (ref "C110") (pin "2") (pinfunction "2_2") (pintype "passive"))
      (node (ref "SV3") (pin "27") (pinfunction "27_27") (pintype "passive"))
    )
    (net (code "121") (name "/OUT46") (class "Default")
      (node (ref "C111") (pin "2") (pinfunction "2_2") (pintype "passive"))
      (node (ref "SV3") (pin "29") (pinfunction "29_29") (pintype "passive"))
    )
    (net (code "122") (name "/OUT47") (class "Default")
      (node (ref "C112") (pin "2") (pinfunction "2_2") (pintype "passive"))
      (node (ref "SV3") (pin "31") (pinfunction "31_31") (pintype "passive"))
    )
    (net (code "123") (name "/OUT48") (class "Default")
      (node (ref "C113") (pin "2") (pinfunction "2_2") (pintype "passive"))
      (node (ref "SV4") (pin "1") (pinfunction "1_1") (pintype "passive"))
    )
    (net (code "124") (name "/OUT49") (class "Default")
      (node (ref "C114") (pin "2") (pinfunction "2_2") (pintype "passive"))
      (node (ref "SV4") (pin "3") (pinfunction "3_3") (pintype "passive"))
    )
    (net (code "125") (name "/OUT50") (class "Default")
      (node (ref "C115") (pin "2") (pinfunction "2_2") (pintype "passive"))
      (node (ref "SV4") (pin "5") (pinfunction "5_5") (pintype "passive"))
    )
    (net (code "126") (name "/OUT51") (class "Default")
      (node (ref "C116") (pin "2") (pinfunction "2_2") (pintype "passive"))
      (node (ref "SV4") (pin "7") (pinfunction "7_7") (pintype "passive"))
    )
    (net (code "127") (name "/OUT52") (class "Default")
      (node (ref "C117") (pin "2") (pinfunction "2_2") (pintype "passive"))
      (node (ref "SV4") (pin "9") (pinfunction "9_9") (pintype "passive"))
    )
    (net (code "128") (name "/OUT53") (class "Default")
      (node (ref "C118") (pin "2") (pinfunction "2_2") (pintype "passive"))
      (node (ref "SV4") (pin "11") (pinfunction "11_11") (pintype "passive"))
    )
    (net (code "129") (name "/OUT54") (class "Default")
      (node (ref "C119") (pin "2") (pinfunction "2_2") (pintype "passive"))
      (node (ref "SV4") (pin "13") (pinfunction "13_13") (pintype "passive"))
    )
    (net (code "130") (name "/OUT55") (class "Default")
      (node (ref "C120") (pin "2") (pinfunction "2_2") (pintype "passive"))
      (node (ref "SV4") (pin "15") (pinfunction "15_15") (pintype "passive"))
    )
    (net (code "131") (name "/OUT56") (class "Default")
      (node (ref "C121") (pin "2") (pinfunction "2_2") (pintype "passive"))
      (node (ref "SV4") (pin "17") (pinfunction "17_17") (pintype "passive"))
    )
    (net (code "132") (name "/OUT57") (class "Default")
      (node (ref "C122") (pin "2") (pinfunction "2_2") (pintype "passive"))
      (node (ref "SV4") (pin "19") (pinfunction "19_19") (pintype "passive"))
    )
    (net (code "133") (name "/OUT58") (class "Default")
      (node (ref "C123") (pin "2") (pinfunction "2_2") (pintype "passive"))
      (node (ref "SV4") (pin "21") (pinfunction "21_21") (pintype "passive"))
    )
    (net (code "134") (name "/OUT59") (class "Default")
      (node (ref "C124") (pin "2") (pinfunction "2_2") (pintype "passive"))
      (node (ref "SV4") (pin "23") (pinfunction "23_23") (pintype "passive"))
    )
    (net (code "135") (name "/OUT60") (class "Default")
      (node (ref "C125") (pin "2") (pinfunction "2_2") (pintype "passive"))
      (node (ref "SV4") (pin "25") (pinfunction "25_25") (pintype "passive"))
    )
    (net (code "136") (name "/OUT61") (class "Default")
      (node (ref "C126") (pin "2") (pinfunction "2_2") (pintype "passive"))
      (node (ref "SV4") (pin "27") (pinfunction "27_27") (pintype "passive"))
    )
    (net (code "137") (name "/OUT62") (class "Default")
      (node (ref "C127") (pin "2") (pinfunction "2_2") (pintype "passive"))
      (node (ref "SV4") (pin "29") (pinfunction "29_29") (pintype "passive"))
    )
    (net (code "138") (name "/OUT63") (class "Default")
      (node (ref "C128") (pin "2") (pinfunction "2_2") (pintype "passive"))
      (node (ref "SV4") (pin "31") (pinfunction "31_31") (pintype "passive"))
    )
    (net (code "139") (name "/RX") (class "Default")
      (node (ref "JP1") (pin "39") (pinfunction "39_39") (pintype "passive"))
      (node (ref "U66") (pin "5") (pinfunction "RXD_5") (pintype "bidirectional"))
    )
    (net (code "140") (name "/TX") (class "Default")
      (node (ref "JP1") (pin "37") (pinfunction "37_37") (pintype "passive"))
      (node (ref "U66") (pin "1") (pinfunction "TXD_1") (pintype "bidirectional"))
    )
    (net (code "141") (name "/TXDEN") (class "Default")
      (node (ref "U66") (pin "13") (pinfunction "CBUS2_13") (pintype "bidirectional"))
    )
    (net (code "142") (name "/VBUS") (class "Default")
      (node (ref "C139") (pin "1") (pinfunction "1_1") (pintype "passive"))
      (node (ref "L1") (pin "A") (pinfunction "1_A") (pintype "passive"))
      (node (ref "X1") (pin "1") (pinfunction "1_1") (pintype "passive"))
    )
    (net (code "143") (name "/VCC") (class "Default")
      (node (ref "C138") (pin "1") (pinfunction "1_1") (pintype "passive"))
      (node (ref "C142") (pin "+") (pinfunction "+_+") (pintype "passive"))
      (node (ref "L2") (pin "C") (pinfunction "2_C") (pintype "passive"))
      (node (ref "U66") (pin "20") (pinfunction "VCC_20") (pintype "power_in"))
    )
    (net (code "144") (name "/VDD") (class "Default")
      (node (ref "C1") (pin "1") (pinfunction "1_1") (pintype "passive"))
      (node (ref "C10") (pin "1") (pinfunction "1_1") (pintype "passive"))
      (node (ref "C11") (pin "1") (pinfunction "1_1") (pintype "passive"))
      (node (ref "C12") (pin "1") (pinfunction "1_1") (pintype "passive"))
      (node (ref "C13") (pin "1") (pinfunction "1_1") (pintype "passive"))
      (node (ref "C130") (pin "+") (pinfunction "+_+") (pintype "passive"))
      (node (ref "C131") (pin "+") (pinfunction "+_+") (pintype "passive"))
      (node (ref "C132") (pin "+") (pinfunction "+_+") (pintype "passive"))
      (node (ref "C134") (pin "1") (pinfunction "1_1") (pintype "passive"))
      (node (ref "C135") (pin "1") (pinfunction "1_1") (pintype "passive"))
      (node (ref "C136") (pin "1") (pinfunction "1_1") (pintype "passive"))
      (node (ref "C14") (pin "1") (pinfunction "1_1") (pintype "passive"))
      (node (ref "C15") (pin "1") (pinfunction "1_1") (pintype "passive"))
      (node (ref "C16") (pin "1") (pinfunction "1_1") (pintype "passive"))
      (node (ref "C17") (pin "1") (pinfunction "1_1") (pintype "passive"))
      (node (ref "C18") (pin "1") (pinfunction "1_1") (pintype "passive"))
      (node (ref "C19") (pin "1") (pinfunction "1_1") (pintype "passive"))
      (node (ref "C2") (pin "1") (pinfunction "1_1") (pintype "passive"))
      (node (ref "C20") (pin "1") (pinfunction "1_1") (pintype "passive"))
      (node (ref "C21") (pin "1") (pinfunction "1_1") (pintype "passive"))
      (node (ref "C22") (pin "1") (pinfunction "1_1") (pintype "passive"))
      (node (ref "C23") (pin "1") (pinfunction "1_1") (pintype "passive"))
      (node (ref "C24") (pin "1") (pinfunction "1_1") (pintype "passive"))
      (node (ref "C25") (pin "1") (pinfunction "1_1") (pintype "passive"))
      (node (ref "C26") (pin "1") (pinfunction "1_1") (pintype "passive"))
      (node (ref "C27") (pin "1") (pinfunction "1_1") (pintype "passive"))
      (node (ref "C28") (pin "1") (pinfunction "1_1") (pintype "passive"))
      (node (ref "C29") (pin "1") (pinfunction "1_1") (pintype "passive"))
      (node (ref "C3") (pin "1") (pinfunction "1_1") (pintype "passive"))
      (node (ref "C30") (pin "1") (pinfunction "1_1") (pintype "passive"))
      (node (ref "C31") (pin "1") (pinfunction "1_1") (pintype "passive"))
      (node (ref "C32") (pin "1") (pinfunction "1_1") (pintype "passive"))
      (node (ref "C33") (pin "1") (pinfunction "1_1") (pintype "passive"))
      (node (ref "C34") (pin "1") (pinfunction "1_1") (pintype "passive"))
      (node (ref "C35") (pin "1") (pinfunction "1_1") (pintype "passive"))
      (node (ref "C36") (pin "1") (pinfunction "1_1") (pintype "passive"))
      (node (ref "C37") (pin "1") (pinfunction "1_1") (pintype "passive"))
      (node (ref "C38") (pin "1") (pinfunction "1_1") (pintype "passive"))
      (node (ref "C39") (pin "1") (pinfunction "1_1") (pintype "passive"))
      (node (ref "C4") (pin "1") (pinfunction "1_1") (pintype "passive"))
      (node (ref "C40") (pin "1") (pinfunction "1_1") (pintype "passive"))
      (node (ref "C41") (pin "1") (pinfunction "1_1") (pintype "passive"))
      (node (ref "C42") (pin "1") (pinfunction "1_1") (pintype "passive"))
      (node (ref "C43") (pin "1") (pinfunction "1_1") (pintype "passive"))
      (node (ref "C44") (pin "1") (pinfunction "1_1") (pintype "passive"))
      (node (ref "C45") (pin "1") (pinfunction "1_1") (pintype "passive"))
      (node (ref "C46") (pin "1") (pinfunction "1_1") (pintype "passive"))
      (node (ref "C47") (pin "1") (pinfunction "1_1") (pintype "passive"))
      (node (ref "C48") (pin "1") (pinfunction "1_1") (pintype "passive"))
      (node (ref "C49") (pin "1") (pinfunction "1_1") (pintype "passive"))
      (node (ref "C5") (pin "1") (pinfunction "1_1") (pintype "passive"))
      (node (ref "C50") (pin "1") (pinfunction "1_1") (pintype "passive"))
      (node (ref "C51") (pin "1") (pinfunction "1_1") (pintype "passive"))
      (node (ref "C52") (pin "1") (pinfunction "1_1") (pintype "passive"))
      (node (ref "C53") (pin "1") (pinfunction "1_1") (pintype "passive"))
      (node (ref "C54") (pin "1") (pinfunction "1_1") (pintype "passive"))
      (node (ref "C55") (pin "1") (pinfunction "1_1") (pintype "passive"))
      (node (ref "C56") (pin "1") (pinfunction "1_1") (pintype "passive"))
      (node (ref "C57") (pin "1") (pinfunction "1_1") (pintype "passive"))
      (node (ref "C58") (pin "1") (pinfunction "1_1") (pintype "passive"))
      (node (ref "C59") (pin "1") (pinfunction "1_1") (pintype "passive"))
      (node (ref "C6") (pin "1") (pinfunction "1_1") (pintype "passive"))
      (node (ref "C60") (pin "1") (pinfunction "1_1") (pintype "passive"))
      (node (ref "C61") (pin "1") (pinfunction "1_1") (pintype "passive"))
      (node (ref "C62") (pin "1") (pinfunction "1_1") (pintype "passive"))
      (node (ref "C63") (pin "1") (pinfunction "1_1") (pintype "passive"))
      (node (ref "C64") (pin "1") (pinfunction "1_1") (pintype "passive"))
      (node (ref "C7") (pin "1") (pinfunction "1_1") (pintype "passive"))
      (node (ref "C8") (pin "1") (pinfunction "1_1") (pintype "passive"))
      (node (ref "C9") (pin "1") (pinfunction "1_1") (pintype "passive"))
      (node (ref "T1") (pin "5") (pinfunction "D_5") (pintype "passive"))
      (node (ref "T1") (pin "6") (pinfunction "D_6") (pintype "passive"))
      (node (ref "U1") (pin "3") (pinfunction "VDD_3") (pintype "power_in"))
      (node (ref "U10") (pin "3") (pinfunction "VDD_3") (pintype "power_in"))
      (node (ref "U11") (pin "3") (pinfunction "VDD_3") (pintype "power_in"))
      (node (ref "U12") (pin "3") (pinfunction "VDD_3") (pintype "power_in"))
      (node (ref "U13") (pin "3") (pinfunction "VDD_3") (pintype "power_in"))
      (node (ref "U14") (pin "3") (pinfunction "VDD_3") (pintype "power_in"))
      (node (ref "U15") (pin "3") (pinfunction "VDD_3") (pintype "power_in"))
      (node (ref "U16") (pin "3") (pinfunction "VDD_3") (pintype "power_in"))
      (node (ref "U17") (pin "3") (pinfunction "VDD_3") (pintype "power_in"))
      (node (ref "U18") (pin "3") (pinfunction "VDD_3") (pintype "power_in"))
      (node (ref "U19") (pin "3") (pinfunction "VDD_3") (pintype "power_in"))
      (node (ref "U2") (pin "3") (pinfunction "VDD_3") (pintype "power_in"))
      (node (ref "U20") (pin "3") (pinfunction "VDD_3") (pintype "power_in"))
      (node (ref "U21") (pin "3") (pinfunction "VDD_3") (pintype "power_in"))
      (node (ref "U22") (pin "3") (pinfunction "VDD_3") (pintype "power_in"))
      (node (ref "U23") (pin "3") (pinfunction "VDD_3") (pintype "power_in"))
      (node (ref "U24") (pin "3") (pinfunction "VDD_3") (pintype "power_in"))
      (node (ref "U25") (pin "3") (pinfunction "VDD_3") (pintype "power_in"))
      (node (ref "U26") (pin "3") (pinfunction "VDD_3") (pintype "power_in"))
      (node (ref "U27") (pin "3") (pinfunction "VDD_3") (pintype "power_in"))
      (node (ref "U28") (pin "3") (pinfunction "VDD_3") (pintype "power_in"))
      (node (ref "U29") (pin "3") (pinfunction "VDD_3") (pintype "power_in"))
      (node (ref "U3") (pin "3") (pinfunction "VDD_3") (pintype "power_in"))
      (node (ref "U30") (pin "3") (pinfunction "VDD_3") (pintype "power_in"))
      (node (ref "U31") (pin "3") (pinfunction "VDD_3") (pintype "power_in"))
      (node (ref "U32") (pin "3") (pinfunction "VDD_3") (pintype "power_in"))
      (node (ref "U33") (pin "3") (pinfunction "VDD_3") (pintype "power_in"))
      (node (ref "U34") (pin "3") (pinfunction "VDD_3") (pintype "power_in"))
      (node (ref "U35") (pin "3") (pinfunction "VDD_3") (pintype "power_in"))
      (node (ref "U36") (pin "3") (pinfunction "VDD_3") (pintype "power_in"))
      (node (ref "U37") (pin "3") (pinfunction "VDD_3") (pintype "power_in"))
      (node (ref "U38") (pin "3") (pinfunction "VDD_3") (pintype "power_in"))
      (node (ref "U39") (pin "3") (pinfunction "VDD_3") (pintype "power_in"))
      (node (ref "U4") (pin "3") (pinfunction "VDD_3") (pintype "power_in"))
      (node (ref "U40") (pin "3") (pinfunction "VDD_3") (pintype "power_in"))
      (node (ref "U41") (pin "3") (pinfunction "VDD_3") (pintype "power_in"))
      (node (ref "U42") (pin "3") (pinfunction "VDD_3") (pintype "power_in"))
      (node (ref "U43") (pin "3") (pinfunction "VDD_3") (pintype "power_in"))
      (node (ref "U44") (pin "3") (pinfunction "VDD_3") (pintype "power_in"))
      (node (ref "U45") (pin "3") (pinfunction "VDD_3") (pintype "power_in"))
      (node (ref "U46") (pin "3") (pinfunction "VDD_3") (pintype "power_in"))
      (node (ref "U47") (pin "3") (pinfunction "VDD_3") (pintype "power_in"))
      (node (ref "U48") (pin "3") (pinfunction "VDD_3") (pintype "power_in"))
      (node (ref "U49") (pin "3") (pinfunction "VDD_3") (pintype "power_in"))
      (node (ref "U5") (pin "3") (pinfunction "VDD_3") (pintype "power_in"))
      (node (ref "U50") (pin "3") (pinfunction "VDD_3") (pintype "power_in"))
      (node (ref "U51") (pin "3") (pinfunction "VDD_3") (pintype "power_in"))
      (node (ref "U52") (pin "3") (pinfunction "VDD_3") (pintype "power_in"))
      (node (ref "U53") (pin "3") (pinfunction "VDD_3") (pintype "power_in"))
      (node (ref "U54") (pin "3") (pinfunction "VDD_3") (pintype "power_in"))
      (node (ref "U55") (pin "3") (pinfunction "VDD_3") (pintype "power_in"))
      (node (ref "U56") (pin "3") (pinfunction "VDD_3") (pintype "power_in"))
      (node (ref "U57") (pin "3") (pinfunction "VDD_3") (pintype "power_in"))
      (node (ref "U58") (pin "3") (pinfunction "VDD_3") (pintype "power_in"))
      (node (ref "U59") (pin "3") (pinfunction "VDD_3") (pintype "power_in"))
      (node (ref "U6") (pin "3") (pinfunction "VDD_3") (pintype "power_in"))
      (node (ref "U60") (pin "3") (pinfunction "VDD_3") (pintype "power_in"))
      (node (ref "U61") (pin "3") (pinfunction "VDD_3") (pintype "power_in"))
      (node (ref "U62") (pin "3") (pinfunction "VDD_3") (pintype "power_in"))
      (node (ref "U63") (pin "3") (pinfunction "VDD_3") (pintype "power_in"))
      (node (ref "U64") (pin "3") (pinfunction "VDD_3") (pintype "power_in"))
      (node (ref "U65") (pin "7") (pinfunction "VOUT_7") (pintype "power_in"))
      (node (ref "U7") (pin "3") (pinfunction "VDD_3") (pintype "power_in"))
      (node (ref "U8") (pin "3") (pinfunction "VDD_3") (pintype "power_in"))
      (node (ref "U9") (pin "3") (pinfunction "VDD_3") (pintype "power_in"))
    )
    (net (code "145") (name "/VIN") (class "Default")
      (node (ref "J1") (pin "1") (pinfunction "1_1") (pintype "passive"))
      (node (ref "R1") (pin "2") (pinfunction "2_2") (pintype "passive"))
      (node (ref "R2") (pin "2") (pinfunction "2_2") (pintype "passive"))
      (node (ref "T1") (pin "7") (pinfunction "D_7") (pintype "passive"))
      (node (ref "T1") (pin "8") (pinfunction "D_8") (pintype "passive"))
      (node (ref "U65") (pin "1") (pinfunction "VIN_1") (pintype "power_in"))
    )
    (net (code "146") (name "/~{PWREN}") (class "Default")
      (node (ref "U66") (pin "14") (pinfunction "CBUS3_14") (pintype "bidirectional"))
    )
    (net (code "147") (name "/~{RXLED}") (class "Default")
      (node (ref "R6") (pin "1") (pinfunction "1_1") (pintype "passive"))
      (node (ref "U66") (pin "22") (pinfunction "CBUS1_22") (pintype "bidirectional"))
    )
    (net (code "148") (name "/~{SLEEP}") (class "Default")
      (node (ref "U66") (pin "12") (pinfunction "CBUS4_12") (pintype "bidirectional"))
    )
    (net (code "149") (name "/~{TXLED}") (class "Default")
      (node (ref "R5") (pin "1") (pinfunction "1_1") (pintype "passive"))
      (node (ref "U66") (pin "23") (pinfunction "CBUS0_23") (pintype "bidirectional"))
    )
    (net (code "150") (name "GND") (class "Default")
      (node (ref "C1") (pin "2") (pinfunction "2_2") (pintype "passive"))
      (node (ref "C10") (pin "2") (pinfunction "2_2") (pintype "passive"))
      (node (ref "C11") (pin "2") (pinfunction "2_2") (pintype "passive"))
      (node (ref "C12") (pin "2") (pinfunction "2_2") (pintype "passive"))
      (node (ref "C13") (pin "2") (pinfunction "2_2") (pintype "passive"))
      (node (ref "C130") (pin "-") (pinfunction "-_-") (pintype "passive"))
      (node (ref "C131") (pin "-") (pinfunction "-_-") (pintype "passive"))
      (node (ref "C132") (pin "-") (pinfunction "-_-") (pintype "passive"))
      (node (ref "C134") (pin "2") (pinfunction "2_2") (pintype "passive"))
      (node (ref "C135") (pin "2") (pinfunction "2_2") (pintype "passive"))
      (node (ref "C136") (pin "2") (pinfunction "2_2") (pintype "passive"))
      (node (ref "C137") (pin "2") (pinfunction "2_2") (pintype "passive"))
      (node (ref "C138") (pin "2") (pinfunction "2_2") (pintype "passive"))
      (node (ref "C139") (pin "2") (pinfunction "2_2") (pintype "passive"))
      (node (ref "C14") (pin "2") (pinfunction "2_2") (pintype "passive"))
      (node (ref "C140") (pin "2") (pinfunction "2_2") (pintype "passive"))
      (node (ref "C141") (pin "2") (pinfunction "2_2") (pintype "passive"))
      (node (ref "C142") (pin "-") (pinfunction "-_-") (pintype "passive"))
      (node (ref "C15") (pin "2") (pinfunction "2_2") (pintype "passive"))
      (node (ref "C16") (pin "2") (pinfunction "2_2") (pintype "passive"))
      (node (ref "C17") (pin "2") (pinfunction "2_2") (pintype "passive"))
      (node (ref "C18") (pin "2") (pinfunction "2_2") (pintype "passive"))
      (node (ref "C19") (pin "2") (pinfunction "2_2") (pintype "passive"))
      (node (ref "C2") (pin "2") (pinfunction "2_2") (pintype "passive"))
      (node (ref "C20") (pin "2") (pinfunction "2_2") (pintype "passive"))
      (node (ref "C21") (pin "2") (pinfunction "2_2") (pintype "passive"))
      (node (ref "C22") (pin "2") (pinfunction "2_2") (pintype "passive"))
      (node (ref "C23") (pin "2") (pinfunction "2_2") (pintype "passive"))
      (node (ref "C24") (pin "2") (pinfunction "2_2") (pintype "passive"))
      (node (ref "C25") (pin "2") (pinfunction "2_2") (pintype "passive"))
      (node (ref "C26") (pin "2") (pinfunction "2_2") (pintype "passive"))
      (node (ref "C27") (pin "2") (pinfunction "2_2") (pintype "passive"))
      (node (ref "C28") (pin "2") (pinfunction "2_2") (pintype "passive"))
      (node (ref "C29") (pin "2") (pinfunction "2_2") (pintype "passive"))
      (node (ref "C3") (pin "2") (pinfunction "2_2") (pintype "passive"))
      (node (ref "C30") (pin "2") (pinfunction "2_2") (pintype "passive"))
      (node (ref "C31") (pin "2") (pinfunction "2_2") (pintype "passive"))
      (node (ref "C32") (pin "2") (pinfunction "2_2") (pintype "passive"))
      (node (ref "C33") (pin "2") (pinfunction "2_2") (pintype "passive"))
      (node (ref "C34") (pin "2") (pinfunction "2_2") (pintype "passive"))
      (node (ref "C35") (pin "2") (pinfunction "2_2") (pintype "passive"))
      (node (ref "C36") (pin "2") (pinfunction "2_2") (pintype "passive"))
      (node (ref "C37") (pin "2") (pinfunction "2_2") (pintype "passive"))
      (node (ref "C38") (pin "2") (pinfunction "2_2") (pintype "passive"))
      (node (ref "C39") (pin "2") (pinfunction "2_2") (pintype "passive"))
      (node (ref "C4") (pin "2") (pinfunction "2_2") (pintype "passive"))
      (node (ref "C40") (pin "2") (pinfunction "2_2") (pintype "passive"))
      (node (ref "C41") (pin "2") (pinfunction "2_2") (pintype "passive"))
      (node (ref "C42") (pin "2") (pinfunction "2_2") (pintype "passive"))
      (node (ref "C43") (pin "2") (pinfunction "2_2") (pintype "passive"))
      (node (ref "C44") (pin "2") (pinfunction "2_2") (pintype "passive"))
      (node (ref "C45") (pin "2") (pinfunction "2_2") (pintype "passive"))
      (node (ref "C46") (pin "2") (pinfunction "2_2") (pintype "passive"))
      (node (ref "C47") (pin "2") (pinfunction "2_2") (pintype "passive"))
      (node (ref "C48") (pin "2") (pinfunction "2_2") (pintype "passive"))
      (node (ref "C49") (pin "2") (pinfunction "2_2") (pintype "passive"))
      (node (ref "C5") (pin "2") (pinfunction "2_2") (pintype "passive"))
      (node (ref "C50") (pin "2") (pinfunction "2_2") (pintype "passive"))
      (node (ref "C51") (pin "2") (pinfunction "2_2") (pintype "passive"))
      (node (ref "C52") (pin "2") (pinfunction "2_2") (pintype "passive"))
      (node (ref "C53") (pin "2") (pinfunction "2_2") (pintype "passive"))
      (node (ref "C54") (pin "2") (pinfunction "2_2") (pintype "passive"))
      (node (ref "C55") (pin "2") (pinfunction "2_2") (pintype "passive"))
      (node (ref "C56") (pin "2") (pinfunction "2_2") (pintype "passive"))
      (node (ref "C57") (pin "2") (pinfunction "2_2") (pintype "passive"))
      (node (ref "C58") (pin "2") (pinfunction "2_2") (pintype "passive"))
      (node (ref "C59") (pin "2") (pinfunction "2_2") (pintype "passive"))
      (node (ref "C6") (pin "2") (pinfunction "2_2") (pintype "passive"))
      (node (ref "C60") (pin "2") (pinfunction "2_2") (pintype "passive"))
      (node (ref "C61") (pin "2") (pinfunction "2_2") (pintype "passive"))
      (node (ref "C62") (pin "2") (pinfunction "2_2") (pintype "passive"))
      (node (ref "C63") (pin "2") (pinfunction "2_2") (pintype "passive"))
      (node (ref "C64") (pin "2") (pinfunction "2_2") (pintype "passive"))
      (node (ref "C7") (pin "2") (pinfunction "2_2") (pintype "passive"))
      (node (ref "C8") (pin "2") (pinfunction "2_2") (pintype "passive"))
      (node (ref "C9") (pin "2") (pinfunction "2_2") (pintype "passive"))
      (node (ref "J1") (pin "2") (pinfunction "2_2") (pintype "passive"))
      (node (ref "J1") (pin "3") (pinfunction "3_3") (pintype "passive"))
      (node (ref "JP1") (pin "11") (pinfunction "11_11") (pintype "passive"))
      (node (ref "JP1") (pin "29") (pinfunction "29_29") (pintype "passive"))
      (node (ref "JP2") (pin "11") (pinfunction "11_11") (pintype "passive"))
      (node (ref "JP2") (pin "29") (pinfunction "29_29") (pintype "passive"))
      (node (ref "JUMPER") (pin "1") (pinfunction "1_1") (pintype "passive"))
      (node (ref "R4") (pin "1") (pinfunction "1_1") (pintype "passive"))
      (node (ref "SV1") (pin "10") (pinfunction "10_10") (pintype "passive"))
      (node (ref "SV1") (pin "12") (pinfunction "12_12") (pintype "passive"))
      (node (ref "SV1") (pin "14") (pinfunction "14_14") (pintype "passive"))
      (node (ref "SV1") (pin "16") (pinfunction "16_16") (pintype "passive"))
      (node (ref "SV1") (pin "18") (pinfunction "18_18") (pintype "passive"))
      (node (ref "SV1") (pin "2") (pinfunction "2_2") (pintype "passive"))
      (node (ref "SV1") (pin "20") (pinfunction "20_20") (pintype "passive"))
      (node (ref "SV1") (pin "22") (pinfunction "22_22") (pintype "passive"))
      (node (ref "SV1") (pin "24") (pinfunction "24_24") (pintype "passive"))
      (node (ref "SV1") (pin "26") (pinfunction "26_26") (pintype "passive"))
      (node (ref "SV1") (pin "28") (pinfunction "28_28") (pintype "passive"))
      (node (ref "SV1") (pin "30") (pinfunction "30_30") (pintype "passive"))
      (node (ref "SV1") (pin "32") (pinfunction "32_32") (pintype "passive"))
      (node (ref "SV1") (pin "4") (pinfunction "4_4") (pintype "passive"))
      (node (ref "SV1") (pin "6") (pinfunction "6_6") (pintype "passive"))
      (node (ref "SV1") (pin "8") (pinfunction "8_8") (pintype "passive"))
      (node (ref "SV2") (pin "10") (pinfunction "10_10") (pintype "passive"))
      (node (ref "SV2") (pin "12") (pinfunction "12_12") (pintype "passive"))
      (node (ref "SV2") (pin "14") (pinfunction "14_14") (pintype "passive"))
      (node (ref "SV2") (pin "16") (pinfunction "16_16") (pintype "passive"))
      (node (ref "SV2") (pin "18") (pinfunction "18_18") (pintype "passive"))
      (node (ref "SV2") (pin "2") (pinfunction "2_2") (pintype "passive"))
      (node (ref "SV2") (pin "20") (pinfunction "20_20") (pintype "passive"))
      (node (ref "SV2") (pin "22") (pinfunction "22_22") (pintype "passive"))
      (node (ref "SV2") (pin "24") (pinfunction "24_24") (pintype "passive"))
      (node (ref "SV2") (pin "26") (pinfunction "26_26") (pintype "passive"))
      (node (ref "SV2") (pin "28") (pinfunction "28_28") (pintype "passive"))
      (node (ref "SV2") (pin "30") (pinfunction "30_30") (pintype "passive"))
      (node (ref "SV2") (pin "32") (pinfunction "32_32") (pintype "passive"))
      (node (ref "SV2") (pin "4") (pinfunction "4_4") (pintype "passive"))
      (node (ref "SV2") (pin "6") (pinfunction "6_6") (pintype "passive"))
      (node (ref "SV2") (pin "8") (pinfunction "8_8") (pintype "passive"))
      (node (ref "SV3") (pin "10") (pinfunction "10_10") (pintype "passive"))
      (node (ref "SV3") (pin "12") (pinfunction "12_12") (pintype "passive"))
      (node (ref "SV3") (pin "14") (pinfunction "14_14") (pintype "passive"))
      (node (ref "SV3") (pin "16") (pinfunction "16_16") (pintype "passive"))
      (node (ref "SV3") (pin "18") (pinfunction "18_18") (pintype "passive"))
      (node (ref "SV3") (pin "2") (pinfunction "2_2") (pintype "passive"))
      (node (ref "SV3") (pin "20") (pinfunction "20_20") (pintype "passive"))
      (node (ref "SV3") (pin "22") (pinfunction "22_22") (pintype "passive"))
      (node (ref "SV3") (pin "24") (pinfunction "24_24") (pintype "passive"))
      (node (ref "SV3") (pin "26") (pinfunction "26_26") (pintype "passive"))
      (node (ref "SV3") (pin "28") (pinfunction "28_28") (pintype "passive"))
      (node (ref "SV3") (pin "30") (pinfunction "30_30") (pintype "passive"))
      (node (ref "SV3") (pin "32") (pinfunction "32_32") (pintype "passive"))
      (node (ref "SV3") (pin "4") (pinfunction "4_4") (pintype "passive"))
      (node (ref "SV3") (pin "6") (pinfunction "6_6") (pintype "passive"))
      (node (ref "SV3") (pin "8") (pinfunction "8_8") (pintype "passive"))
      (node (ref "SV4") (pin "10") (pinfunction "10_10") (pintype "passive"))
      (node (ref "SV4") (pin "12") (pinfunction "12_12") (pintype "passive"))
      (node (ref "SV4") (pin "14") (pinfunction "14_14") (pintype "passive"))
      (node (ref "SV4") (pin "16") (pinfunction "16_16") (pintype "passive"))
      (node (ref "SV4") (pin "18") (pinfunction "18_18") (pintype "passive"))
      (node (ref "SV4") (pin "2") (pinfunction "2_2") (pintype "passive"))
      (node (ref "SV4") (pin "20") (pinfunction "20_20") (pintype "passive"))
      (node (ref "SV4") (pin "22") (pinfunction "22_22") (pintype "passive"))
      (node (ref "SV4") (pin "24") (pinfunction "24_24") (pintype "passive"))
      (node (ref "SV4") (pin "26") (pinfunction "26_26") (pintype "passive"))
      (node (ref "SV4") (pin "28") (pinfunction "28_28") (pintype "passive"))
      (node (ref "SV4") (pin "30") (pinfunction "30_30") (pintype "passive"))
      (node (ref "SV4") (pin "32") (pinfunction "32_32") (pintype "passive"))
      (node (ref "SV4") (pin "4") (pinfunction "4_4") (pintype "passive"))
      (node (ref "SV4") (pin "6") (pinfunction "6_6") (pintype "passive"))
      (node (ref "SV4") (pin "8") (pinfunction "8_8") (pintype "passive"))
      (node (ref "U1") (pin "4") (pinfunction "GND_4") (pintype "power_in"))
      (node (ref "U10") (pin "4") (pinfunction "GND_4") (pintype "power_in"))
      (node (ref "U11") (pin "4") (pinfunction "GND_4") (pintype "power_in"))
      (node (ref "U12") (pin "4") (pinfunction "GND_4") (pintype "power_in"))
      (node (ref "U13") (pin "4") (pinfunction "GND_4") (pintype "power_in"))
      (node (ref "U14") (pin "4") (pinfunction "GND_4") (pintype "power_in"))
      (node (ref "U15") (pin "4") (pinfunction "GND_4") (pintype "power_in"))
      (node (ref "U16") (pin "4") (pinfunction "GND_4") (pintype "power_in"))
      (node (ref "U17") (pin "4") (pinfunction "GND_4") (pintype "power_in"))
      (node (ref "U18") (pin "4") (pinfunction "GND_4") (pintype "power_in"))
      (node (ref "U19") (pin "4") (pinfunction "GND_4") (pintype "power_in"))
      (node (ref "U2") (pin "4") (pinfunction "GND_4") (pintype "power_in"))
      (node (ref "U20") (pin "4") (pinfunction "GND_4") (pintype "power_in"))
      (node (ref "U21") (pin "4") (pinfunction "GND_4") (pintype "power_in"))
      (node (ref "U22") (pin "4") (pinfunction "GND_4") (pintype "power_in"))
      (node (ref "U23") (pin "4") (pinfunction "GND_4") (pintype "power_in"))
      (node (ref "U24") (pin "4") (pinfunction "GND_4") (pintype "power_in"))
      (node (ref "U25") (pin "4") (pinfunction "GND_4") (pintype "power_in"))
      (node (ref "U26") (pin "4") (pinfunction "GND_4") (pintype "power_in"))
      (node (ref "U27") (pin "4") (pinfunction "GND_4") (pintype "power_in"))
      (node (ref "U28") (pin "4") (pinfunction "GND_4") (pintype "power_in"))
      (node (ref "U29") (pin "4") (pinfunction "GND_4") (pintype "power_in"))
      (node (ref "U3") (pin "4") (pinfunction "GND_4") (pintype "power_in"))
      (node (ref "U30") (pin "4") (pinfunction "GND_4") (pintype "power_in"))
      (node (ref "U31") (pin "4") (pinfunction "GND_4") (pintype "power_in"))
      (node (ref "U32") (pin "4") (pinfunction "GND_4") (pintype "power_in"))
      (node (ref "U33") (pin "4") (pinfunction "GND_4") (pintype "power_in"))
      (node (ref "U34") (pin "4") (pinfunction "GND_4") (pintype "power_in"))
      (node (ref "U35") (pin "4") (pinfunction "GND_4") (pintype "power_in"))
      (node (ref "U36") (pin "4") (pinfunction "GND_4") (pintype "power_in"))
      (node (ref "U37") (pin "4") (pinfunction "GND_4") (pintype "power_in"))
      (node (ref "U38") (pin "4") (pinfunction "GND_4") (pintype "power_in"))
      (node (ref "U39") (pin "4") (pinfunction "GND_4") (pintype "power_in"))
      (node (ref "U4") (pin "4") (pinfunction "GND_4") (pintype "power_in"))
      (node (ref "U40") (pin "4") (pinfunction "GND_4") (pintype "power_in"))
      (node (ref "U41") (pin "4") (pinfunction "GND_4") (pintype "power_in"))
      (node (ref "U42") (pin "4") (pinfunction "GND_4") (pintype "power_in"))
      (node (ref "U43") (pin "4") (pinfunction "GND_4") (pintype "power_in"))
      (node (ref "U44") (pin "4") (pinfunction "GND_4") (pintype "power_in"))
      (node (ref "U45") (pin "4") (pinfunction "GND_4") (pintype "power_in"))
      (node (ref "U46") (pin "4") (pinfunction "GND_4") (pintype "power_in"))
      (node (ref "U47") (pin "4") (pinfunction "GND_4") (pintype "power_in"))
      (node (ref "U48") (pin "4") (pinfunction "GND_4") (pintype "power_in"))
      (node (ref "U49") (pin "4") (pinfunction "GND_4") (pintype "power_in"))
      (node (ref "U5") (pin "4") (pinfunction "GND_4") (pintype "power_in"))
      (node (ref "U50") (pin "4") (pinfunction "GND_4") (pintype "power_in"))
      (node (ref "U51") (pin "4") (pinfunction "GND_4") (pintype "power_in"))
      (node (ref "U52") (pin "4") (pinfunction "GND_4") (pintype "power_in"))
      (node (ref "U53") (pin "4") (pinfunction "GND_4") (pintype "power_in"))
      (node (ref "U54") (pin "4") (pinfunction "GND_4") (pintype "power_in"))
      (node (ref "U55") (pin "4") (pinfunction "GND_4") (pintype "power_in"))
      (node (ref "U56") (pin "4") (pinfunction "GND_4") (pintype "power_in"))
      (node (ref "U57") (pin "4") (pinfunction "GND_4") (pintype "power_in"))
      (node (ref "U58") (pin "4") (pinfunction "GND_4") (pintype "power_in"))
      (node (ref "U59") (pin "4") (pinfunction "GND_4") (pintype "power_in"))
      (node (ref "U6") (pin "4") (pinfunction "GND_4") (pintype "power_in"))
      (node (ref "U60") (pin "4") (pinfunction "GND_4") (pintype "power_in"))
      (node (ref "U61") (pin "4") (pinfunction "GND_4") (pintype "power_in"))
      (node (ref "U62") (pin "4") (pinfunction "GND_4") (pintype "power_in"))
      (node (ref "U63") (pin "4") (pinfunction "GND_4") (pintype "power_in"))
      (node (ref "U64") (pin "4") (pinfunction "GND_4") (pintype "power_in"))
      (node (ref "U65") (pin "4") (pinfunction "GND_4") (pintype "power_in"))
      (node (ref "U66") (pin "18") (pinfunction "GND_18") (pintype "power_in"))
      (node (ref "U66") (pin "21") (pinfunction "GND_21") (pintype "power_in"))
      (node (ref "U66") (pin "25") (pinfunction "AGND_25") (pintype "power_in"))
      (node (ref "U66") (pin "26") (pinfunction "TEST_26") (pintype "bidirectional"))
      (node (ref "U66") (pin "7") (pinfunction "GND_7") (pintype "power_in"))
      (node (ref "U7") (pin "4") (pinfunction "GND_4") (pintype "power_in"))
      (node (ref "U8") (pin "4") (pinfunction "GND_4") (pintype "power_in"))
      (node (ref "U9") (pin "4") (pinfunction "GND_4") (pintype "power_in"))
      (node (ref "X1") (pin "5") (pinfunction "5_5") (pintype "passive"))
      (node (ref "X2") (pin "2") (pinfunction "2_2") (pintype "passive"))
    )
    (net (code "151") (name "Net-(L1-2)") (class "Default")
      (node (ref "D1") (pin "P") (pinfunction "P_P") (pintype "passive"))
      (node (ref "L1") (pin "C") (pinfunction "2_C") (pintype "passive"))
    )
    (net (code "152") (name "Net-(L2-1)") (class "Default")
      (node (ref "D1") (pin "N") (pinfunction "N_N") (pintype "passive"))
      (node (ref "L2") (pin "A") (pinfunction "1_A") (pintype "passive"))
    )
    (net (code "153") (name "Net-(LED1-PadC)") (class "Default")
      (node (ref "LED1") (pin "C") (pinfunction "C_C") (pintype "passive"))
      (node (ref "R5") (pin "2") (pinfunction "2_2") (pintype "passive"))
    )
    (net (code "154") (name "Net-(LED2-PadC)") (class "Default")
      (node (ref "LED2") (pin "C") (pinfunction "C_C") (pintype "passive"))
      (node (ref "R6") (pin "2") (pinfunction "2_2") (pintype "passive"))
    )
    (net (code "155") (name "Net-(T1A-G)") (class "Default")
      (node (ref "T1") (pin "2") (pinfunction "G_2") (pintype "passive"))
      (node (ref "T1") (pin "4") (pinfunction "G_4") (pintype "passive"))
      (node (ref "U65") (pin "8") (pinfunction "GATE_8") (pintype "output"))
    )
    (net (code "156") (name "Net-(T1A-S)") (class "Default")
      (node (ref "T1") (pin "1") (pinfunction "S_1") (pintype "passive"))
      (node (ref "T1") (pin "3") (pinfunction "S_3") (pintype "passive"))
    )
    (net (code "157") (name "Net-(U1-OUTH)") (class "Default")
      (node (ref "C65") (pin "1") (pinfunction "1_1") (pintype "passive"))
      (node (ref "U1") (pin "5") (pinfunction "OUTL_5") (pintype "power_in"))
      (node (ref "U1") (pin "6") (pinfunction "OUTH_6") (pintype "power_in"))
    )
    (net (code "158") (name "Net-(U2-OUTH)") (class "Default")
      (node (ref "C66") (pin "1") (pinfunction "1_1") (pintype "passive"))
      (node (ref "U2") (pin "5") (pinfunction "OUTL_5") (pintype "power_in"))
      (node (ref "U2") (pin "6") (pinfunction "OUTH_6") (pintype "power_in"))
    )
    (net (code "159") (name "Net-(U3-OUTH)") (class "Default")
      (node (ref "C67") (pin "1") (pinfunction "1_1") (pintype "passive"))
      (node (ref "U3") (pin "5") (pinfunction "OUTL_5") (pintype "power_in"))
      (node (ref "U3") (pin "6") (pinfunction "OUTH_6") (pintype "power_in"))
    )
    (net (code "160") (name "Net-(U4-OUTH)") (class "Default")
      (node (ref "C68") (pin "1") (pinfunction "1_1") (pintype "passive"))
      (node (ref "U4") (pin "5") (pinfunction "OUTL_5") (pintype "power_in"))
      (node (ref "U4") (pin "6") (pinfunction "OUTH_6") (pintype "power_in"))
    )
    (net (code "161") (name "Net-(U5-OUTH)") (class "Default")
      (node (ref "C69") (pin "1") (pinfunction "1_1") (pintype "passive"))
      (node (ref "U5") (pin "5") (pinfunction "OUTL_5") (pintype "power_in"))
      (node (ref "U5") (pin "6") (pinfunction "OUTH_6") (pintype "power_in"))
    )
    (net (code "162") (name "Net-(U6-OUTH)") (class "Default")
      (node (ref "C70") (pin "1") (pinfunction "1_1") (pintype "passive"))
      (node (ref "U6") (pin "5") (pinfunction "OUTL_5") (pintype "power_in"))
      (node (ref "U6") (pin "6") (pinfunction "OUTH_6") (pintype "power_in"))
    )
    (net (code "163") (name "Net-(U7-OUTH)") (class "Default")
      (node (ref "C71") (pin "1") (pinfunction "1_1") (pintype "passive"))
      (node (ref "U7") (pin "5") (pinfunction "OUTL_5") (pintype "power_in"))
      (node (ref "U7") (pin "6") (pinfunction "OUTH_6") (pintype "power_in"))
    )
    (net (code "164") (name "Net-(U8-OUTH)") (class "Default")
      (node (ref "C72") (pin "1") (pinfunction "1_1") (pintype "passive"))
      (node (ref "U8") (pin "5") (pinfunction "OUTL_5") (pintype "power_in"))
      (node (ref "U8") (pin "6") (pinfunction "OUTH_6") (pintype "power_in"))
    )
    (net (code "165") (name "Net-(U9-OUTH)") (class "Default")
      (node (ref "C73") (pin "1") (pinfunction "1_1") (pintype "passive"))
      (node (ref "U9") (pin "5") (pinfunction "OUTL_5") (pintype "power_in"))
      (node (ref "U9") (pin "6") (pinfunction "OUTH_6") (pintype "power_in"))
    )
    (net (code "166") (name "Net-(U10-OUTH)") (class "Default")
      (node (ref "C74") (pin "1") (pinfunction "1_1") (pintype "passive"))
      (node (ref "U10") (pin "5") (pinfunction "OUTL_5") (pintype "power_in"))
      (node (ref "U10") (pin "6") (pinfunction "OUTH_6") (pintype "power_in"))
    )
    (net (code "167") (name "Net-(U11-OUTH)") (class "Default")
      (node (ref "C75") (pin "1") (pinfunction "1_1") (pintype "passive"))
      (node (ref "U11") (pin "5") (pinfunction "OUTL_5") (pintype "power_in"))
      (node (ref "U11") (pin "6") (pinfunction "OUTH_6") (pintype "power_in"))
    )
    (net (code "168") (name "Net-(U12-OUTH)") (class "Default")
      (node (ref "C76") (pin "1") (pinfunction "1_1") (pintype "passive"))
      (node (ref "U12") (pin "5") (pinfunction "OUTL_5") (pintype "power_in"))
      (node (ref "U12") (pin "6") (pinfunction "OUTH_6") (pintype "power_in"))
    )
    (net (code "169") (name "Net-(U13-OUTH)") (class "Default")
      (node (ref "C77") (pin "1") (pinfunction "1_1") (pintype "passive"))
      (node (ref "U13") (pin "5") (pinfunction "OUTL_5") (pintype "power_in"))
      (node (ref "U13") (pin "6") (pinfunction "OUTH_6") (pintype "power_in"))
    )
    (net (code "170") (name "Net-(U14-OUTH)") (class "Default")
      (node (ref "C78") (pin "1") (pinfunction "1_1") (pintype "passive"))
      (node (ref "U14") (pin "5") (pinfunction "OUTL_5") (pintype "power_in"))
      (node (ref "U14") (pin "6") (pinfunction "OUTH_6") (pintype "power_in"))
    )
    (net (code "171") (name "Net-(U15-OUTH)") (class "Default")
      (node (ref "C79") (pin "1") (pinfunction "1_1") (pintype "passive"))
      (node (ref "U15") (pin "5") (pinfunction "OUTL_5") (pintype "power_in"))
      (node (ref "U15") (pin "6") (pinfunction "OUTH_6") (pintype "power_in"))
    )
    (net (code "172") (name "Net-(U16-OUTH)") (class "Default")
      (node (ref "C80") (pin "1") (pinfunction "1_1") (pintype "passive"))
      (node (ref "U16") (pin "5") (pinfunction "OUTL_5") (pintype "power_in"))
      (node (ref "U16") (pin "6") (pinfunction "OUTH_6") (pintype "power_in"))
    )
    (net (code "173") (name "Net-(U17-OUTH)") (class "Default")
      (node (ref "C81") (pin "1") (pinfunction "1_1") (pintype "passive"))
      (node (ref "U17") (pin "5") (pinfunction "OUTL_5") (pintype "power_in"))
      (node (ref "U17") (pin "6") (pinfunction "OUTH_6") (pintype "power_in"))
    )
    (net (code "174") (name "Net-(U18-OUTH)") (class "Default")
      (node (ref "C82") (pin "1") (pinfunction "1_1") (pintype "passive"))
      (node (ref "U18") (pin "5") (pinfunction "OUTL_5") (pintype "power_in"))
      (node (ref "U18") (pin "6") (pinfunction "OUTH_6") (pintype "power_in"))
    )
    (net (code "175") (name "Net-(U19-OUTH)") (class "Default")
      (node (ref "C83") (pin "1") (pinfunction "1_1") (pintype "passive"))
      (node (ref "U19") (pin "5") (pinfunction "OUTL_5") (pintype "power_in"))
      (node (ref "U19") (pin "6") (pinfunction "OUTH_6") (pintype "power_in"))
    )
    (net (code "176") (name "Net-(U20-OUTH)") (class "Default")
      (node (ref "C84") (pin "1") (pinfunction "1_1") (pintype "passive"))
      (node (ref "U20") (pin "5") (pinfunction "OUTL_5") (pintype "power_in"))
      (node (ref "U20") (pin "6") (pinfunction "OUTH_6") (pintype "power_in"))
    )
    (net (code "177") (name "Net-(U21-OUTH)") (class "Default")
      (node (ref "C85") (pin "1") (pinfunction "1_1") (pintype "passive"))
      (node (ref "U21") (pin "5") (pinfunction "OUTL_5") (pintype "power_in"))
      (node (ref "U21") (pin "6") (pinfunction "OUTH_6") (pintype "power_in"))
    )
    (net (code "178") (name "Net-(U22-OUTH)") (class "Default")
      (node (ref "C86") (pin "1") (pinfunction "1_1") (pintype "passive"))
      (node (ref "U22") (pin "5") (pinfunction "OUTL_5") (pintype "power_in"))
      (node (ref "U22") (pin "6") (pinfunction "OUTH_6") (pintype "power_in"))
    )
    (net (code "179") (name "Net-(U23-OUTH)") (class "Default")
      (node (ref "C87") (pin "1") (pinfunction "1_1") (pintype "passive"))
      (node (ref "U23") (pin "5") (pinfunction "OUTL_5") (pintype "power_in"))
      (node (ref "U23") (pin "6") (pinfunction "OUTH_6") (pintype "power_in"))
    )
    (net (code "180") (name "Net-(U24-OUTH)") (class "Default")
      (node (ref "C88") (pin "1") (pinfunction "1_1") (pintype "passive"))
      (node (ref "U24") (pin "5") (pinfunction "OUTL_5") (pintype "power_in"))
      (node (ref "U24") (pin "6") (pinfunction "OUTH_6") (pintype "power_in"))
    )
    (net (code "181") (name "Net-(U25-OUTH)") (class "Default")
      (node (ref "C89") (pin "1") (pinfunction "1_1") (pintype "passive"))
      (node (ref "U25") (pin "5") (pinfunction "OUTL_5") (pintype "power_in"))
      (node (ref "U25") (pin "6") (pinfunction "OUTH_6") (pintype "power_in"))
    )
    (net (code "182") (name "Net-(U26-OUTH)") (class "Default")
      (node (ref "C90") (pin "1") (pinfunction "1_1") (pintype "passive"))
      (node (ref "U26") (pin "5") (pinfunction "OUTL_5") (pintype "power_in"))
      (node (ref "U26") (pin "6") (pinfunction "OUTH_6") (pintype "power_in"))
    )
    (net (code "183") (name "Net-(U27-OUTH)") (class "Default")
      (node (ref "C91") (pin "1") (pinfunction "1_1") (pintype "passive"))
      (node (ref "U27") (pin "5") (pinfunction "OUTL_5") (pintype "power_in"))
      (node (ref "U27") (pin "6") (pinfunction "OUTH_6") (pintype "power_in"))
    )
    (net (code "184") (name "Net-(U28-OUTH)") (class "Default")
      (node (ref "C92") (pin "1") (pinfunction "1_1") (pintype "passive"))
      (node (ref "U28") (pin "5") (pinfunction "OUTL_5") (pintype "power_in"))
      (node (ref "U28") (pin "6") (pinfunction "OUTH_6") (pintype "power_in"))
    )
    (net (code "185") (name "Net-(U29-OUTH)") (class "Default")
      (node (ref "C93") (pin "1") (pinfunction "1_1") (pintype "passive"))
      (node (ref "U29") (pin "5") (pinfunction "OUTL_5") (pintype "power_in"))
      (node (ref "U29") (pin "6") (pinfunction "OUTH_6") (pintype "power_in"))
    )
    (net (code "186") (name "Net-(U30-OUTH)") (class "Default")
      (node (ref "C94") (pin "1") (pinfunction "1_1") (pintype "passive"))
      (node (ref "U30") (pin "5") (pinfunction "OUTL_5") (pintype "power_in"))
      (node (ref "U30") (pin "6") (pinfunction "OUTH_6") (pintype "power_in"))
    )
    (net (code "187") (name "Net-(U31-OUTH)") (class "Default")
      (node (ref "C95") (pin "1") (pinfunction "1_1") (pintype "passive"))
      (node (ref "U31") (pin "5") (pinfunction "OUTL_5") (pintype "power_in"))
      (node (ref "U31") (pin "6") (pinfunction "OUTH_6") (pintype "power_in"))
    )
    (net (code "188") (name "Net-(U32-OUTH)") (class "Default")
      (node (ref "C96") (pin "1") (pinfunction "1_1") (pintype "passive"))
      (node (ref "U32") (pin "5") (pinfunction "OUTL_5") (pintype "power_in"))
      (node (ref "U32") (pin "6") (pinfunction "OUTH_6") (pintype "power_in"))
    )
    (net (code "189") (name "Net-(U33-OUTH)") (class "Default")
      (node (ref "C97") (pin "1") (pinfunction "1_1") (pintype "passive"))
      (node (ref "U33") (pin "5") (pinfunction "OUTL_5") (pintype "power_in"))
      (node (ref "U33") (pin "6") (pinfunction "OUTH_6") (pintype "power_in"))
    )
    (net (code "190") (name "Net-(U34-OUTH)") (class "Default")
      (node (ref "C98") (pin "1") (pinfunction "1_1") (pintype "passive"))
      (node (ref "U34") (pin "5") (pinfunction "OUTL_5") (pintype "power_in"))
      (node (ref "U34") (pin "6") (pinfunction "OUTH_6") (pintype "power_in"))
    )
    (net (code "191") (name "Net-(U35-OUTH)") (class "Default")
      (node (ref "C99") (pin "1") (pinfunction "1_1") (pintype "passive"))
      (node (ref "U35") (pin "5") (pinfunction "OUTL_5") (pintype "power_in"))
      (node (ref "U35") (pin "6") (pinfunction "OUTH_6") (pintype "power_in"))
    )
    (net (code "192") (name "Net-(U36-OUTH)") (class "Default")
      (node (ref "C100") (pin "1") (pinfunction "1_1") (pintype "passive"))
      (node (ref "U36") (pin "5") (pinfunction "OUTL_5") (pintype "power_in"))
      (node (ref "U36") (pin "6") (pinfunction "OUTH_6") (pintype "power_in"))
    )
    (net (code "193") (name "Net-(U37-OUTH)") (class "Default")
      (node (ref "C101") (pin "1") (pinfunction "1_1") (pintype "passive"))
      (node (ref "U37") (pin "5") (pinfunction "OUTL_5") (pintype "power_in"))
      (node (ref "U37") (pin "6") (pinfunction "OUTH_6") (pintype "power_in"))
    )
    (net (code "194") (name "Net-(U38-OUTH)") (class "Default")
      (node (ref "C102") (pin "1") (pinfunction "1_1") (pintype "passive"))
      (node (ref "U38") (pin "5") (pinfunction "OUTL_5") (pintype "power_in"))
      (node (ref "U38") (pin "6") (pinfunction "OUTH_6") (pintype "power_in"))
    )
    (net (code "195") (name "Net-(U39-OUTH)") (class "Default")
      (node (ref "C103") (pin "1") (pinfunction "1_1") (pintype "passive"))
      (node (ref "U39") (pin "5") (pinfunction "OUTL_5") (pintype "power_in"))
      (node (ref "U39") (pin "6") (pinfunction "OUTH_6") (pintype "power_in"))
    )
    (net (code "196") (name "Net-(U40-OUTH)") (class "Default")
      (node (ref "C104") (pin "1") (pinfunction "1_1") (pintype "passive"))
      (node (ref "U40") (pin "5") (pinfunction "OUTL_5") (pintype "power_in"))
      (node (ref "U40") (pin "6") (pinfunction "OUTH_6") (pintype "power_in"))
    )
    (net (code "197") (name "Net-(U41-OUTH)") (class "Default")
      (node (ref "C105") (pin "1") (pinfunction "1_1") (pintype "passive"))
      (node (ref "U41") (pin "5") (pinfunction "OUTL_5") (pintype "power_in"))
      (node (ref "U41") (pin "6") (pinfunction "OUTH_6") (pintype "power_in"))
    )
    (net (code "198") (name "Net-(U42-OUTH)") (class "Default")
      (node (ref "C106") (pin "1") (pinfunction "1_1") (pintype "passive"))
      (node (ref "U42") (pin "5") (pinfunction "OUTL_5") (pintype "power_in"))
      (node (ref "U42") (pin "6") (pinfunction "OUTH_6") (pintype "power_in"))
    )
    (net (code "199") (name "Net-(U43-OUTH)") (class "Default")
      (node (ref "C107") (pin "1") (pinfunction "1_1") (pintype "passive"))
      (node (ref "U43") (pin "5") (pinfunction "OUTL_5") (pintype "power_in"))
      (node (ref "U43") (pin "6") (pinfunction "OUTH_6") (pintype "power_in"))
    )
    (net (code "200") (name "Net-(U44-OUTH)") (class "Default")
      (node (ref "C108") (pin "1") (pinfunction "1_1") (pintype "passive"))
      (node (ref "U44") (pin "5") (pinfunction "OUTL_5") (pintype "power_in"))
      (node (ref "U44") (pin "6") (pinfunction "OUTH_6") (pintype "power_in"))
    )
    (net (code "201") (name "Net-(U45-OUTH)") (class "Default")
      (node (ref "C109") (pin "1") (pinfunction "1_1") (pintype "passive"))
      (node (ref "U45") (pin "5") (pinfunction "OUTL_5") (pintype "power_in"))
      (node (ref "U45") (pin "6") (pinfunction "OUTH_6") (pintype "power_in"))
    )
    (net (code "202") (name "Net-(U46-OUTH)") (class "Default")
      (node (ref "C110") (pin "1") (pinfunction "1_1") (pintype "passive"))
      (node (ref "U46") (pin "5") (pinfunction "OUTL_5") (pintype "power_in"))
      (node (ref "U46") (pin "6") (pinfunction "OUTH_6") (pintype "power_in"))
    )
    (net (code "203") (name "Net-(U47-OUTH)") (class "Default")
      (node (ref "C111") (pin "1") (pinfunction "1_1") (pintype "passive"))
      (node (ref "U47") (pin "5") (pinfunction "OUTL_5") (pintype "power_in"))
      (node (ref "U47") (pin "6") (pinfunction "OUTH_6") (pintype "power_in"))
    )
    (net (code "204") (name "Net-(U48-OUTH)") (class "Default")
      (node (ref "C112") (pin "1") (pinfunction "1_1") (pintype "passive"))
      (node (ref "U48") (pin "5") (pinfunction "OUTL_5") (pintype "power_in"))
      (node (ref "U48") (pin "6") (pinfunction "OUTH_6") (pintype "power_in"))
    )
    (net (code "205") (name "Net-(U49-OUTH)") (class "Default")
      (node (ref "C113") (pin "1") (pinfunction "1_1") (pintype "passive"))
      (node (ref "U49") (pin "5") (pinfunction "OUTL_5") (pintype "power_in"))
      (node (ref "U49") (pin "6") (pinfunction "OUTH_6") (pintype "power_in"))
    )
    (net (code "206") (name "Net-(U50-OUTH)") (class "Default")
      (node (ref "C114") (pin "1") (pinfunction "1_1") (pintype "passive"))
      (node (ref "U50") (pin "5") (pinfunction "OUTL_5") (pintype "power_in"))
      (node (ref "U50") (pin "6") (pinfunction "OUTH_6") (pintype "power_in"))
    )
    (net (code "207") (name "Net-(U51-OUTH)") (class "Default")
      (node (ref "C115") (pin "1") (pinfunction "1_1") (pintype "passive"))
      (node (ref "U51") (pin "5") (pinfunction "OUTL_5") (pintype "power_in"))
      (node (ref "U51") (pin "6") (pinfunction "OUTH_6") (pintype "power_in"))
    )
    (net (code "208") (name "Net-(U52-OUTH)") (class "Default")
      (node (ref "C116") (pin "1") (pinfunction "1_1") (pintype "passive"))
      (node (ref "U52") (pin "5") (pinfunction "OUTL_5") (pintype "power_in"))
      (node (ref "U52") (pin "6") (pinfunction "OUTH_6") (pintype "power_in"))
    )
    (net (code "209") (name "Net-(U53-OUTH)") (class "Default")
      (node (ref "C117") (pin "1") (pinfunction "1_1") (pintype "passive"))
      (node (ref "U53") (pin "5") (pinfunction "OUTL_5") (pintype "power_in"))
      (node (ref "U53") (pin "6") (pinfunction "OUTH_6") (pintype "power_in"))
    )
    (net (code "210") (name "Net-(U54-OUTH)") (class "Default")
      (node (ref "C118") (pin "1") (pinfunction "1_1") (pintype "passive"))
      (node (ref "U54") (pin "5") (pinfunction "OUTL_5") (pintype "power_in"))
      (node (ref "U54") (pin "6") (pinfunction "OUTH_6") (pintype "power_in"))
    )
    (net (code "211") (name "Net-(U55-OUTH)") (class "Default")
      (node (ref "C119") (pin "1") (pinfunction "1_1") (pintype "passive"))
      (node (ref "U55") (pin "5") (pinfunction "OUTL_5") (pintype "power_in"))
      (node (ref "U55") (pin "6") (pinfunction "OUTH_6") (pintype "power_in"))
    )
    (net (code "212") (name "Net-(U56-OUTH)") (class "Default")
      (node (ref "C120") (pin "1") (pinfunction "1_1") (pintype "passive"))
      (node (ref "U56") (pin "5") (pinfunction "OUTL_5") (pintype "power_in"))
      (node (ref "U56") (pin "6") (pinfunction "OUTH_6") (pintype "power_in"))
    )
    (net (code "213") (name "Net-(U57-OUTH)") (class "Default")
      (node (ref "C121") (pin "1") (pinfunction "1_1") (pintype "passive"))
      (node (ref "U57") (pin "5") (pinfunction "OUTL_5") (pintype "power_in"))
      (node (ref "U57") (pin "6") (pinfunction "OUTH_6") (pintype "power_in"))
    )
    (net (code "214") (name "Net-(U58-OUTH)") (class "Default")
      (node (ref "C122") (pin "1") (pinfunction "1_1") (pintype "passive"))
      (node (ref "U58") (pin "5") (pinfunction "OUTL_5") (pintype "power_in"))
      (node (ref "U58") (pin "6") (pinfunction "OUTH_6") (pintype "power_in"))
    )
    (net (code "215") (name "Net-(U59-OUTH)") (class "Default")
      (node (ref "C123") (pin "1") (pinfunction "1_1") (pintype "passive"))
      (node (ref "U59") (pin "5") (pinfunction "OUTL_5") (pintype "power_in"))
      (node (ref "U59") (pin "6") (pinfunction "OUTH_6") (pintype "power_in"))
    )
    (net (code "216") (name "Net-(U60-OUTH)") (class "Default")
      (node (ref "C124") (pin "1") (pinfunction "1_1") (pintype "passive"))
      (node (ref "U60") (pin "5") (pinfunction "OUTL_5") (pintype "power_in"))
      (node (ref "U60") (pin "6") (pinfunction "OUTH_6") (pintype "power_in"))
    )
    (net (code "217") (name "Net-(U61-OUTH)") (class "Default")
      (node (ref "C125") (pin "1") (pinfunction "1_1") (pintype "passive"))
      (node (ref "U61") (pin "5") (pinfunction "OUTL_5") (pintype "power_in"))
      (node (ref "U61") (pin "6") (pinfunction "OUTH_6") (pintype "power_in"))
    )
    (net (code "218") (name "Net-(U62-OUTH)") (class "Default")
      (node (ref "C126") (pin "1") (pinfunction "1_1") (pintype "passive"))
      (node (ref "U62") (pin "5") (pinfunction "OUTL_5") (pintype "power_in"))
      (node (ref "U62") (pin "6") (pinfunction "OUTH_6") (pintype "power_in"))
    )
    (net (code "219") (name "Net-(U63-OUTH)") (class "Default")
      (node (ref "C127") (pin "1") (pinfunction "1_1") (pintype "passive"))
      (node (ref "U63") (pin "5") (pinfunction "OUTL_5") (pintype "power_in"))
      (node (ref "U63") (pin "6") (pinfunction "OUTH_6") (pintype "power_in"))
    )
    (net (code "220") (name "Net-(U64-OUTH)") (class "Default")
      (node (ref "C128") (pin "1") (pinfunction "1_1") (pintype "passive"))
      (node (ref "U64") (pin "5") (pinfunction "OUTL_5") (pintype "power_in"))
      (node (ref "U64") (pin "6") (pinfunction "OUTH_6") (pintype "power_in"))
    )
    (net (code "221") (name "Net-(U65-OV)") (class "Default")
      (node (ref "R3") (pin "1") (pinfunction "1_1") (pintype "passive"))
      (node (ref "R4") (pin "2") (pinfunction "2_2") (pintype "passive"))
      (node (ref "U65") (pin "3") (pinfunction "OV_3") (pintype "input"))
    )
    (net (code "222") (name "Net-(U65-UV)") (class "Default")
      (node (ref "R2") (pin "1") (pinfunction "1_1") (pintype "passive"))
      (node (ref "R3") (pin "2") (pinfunction "2_2") (pintype "passive"))
      (node (ref "U65") (pin "2") (pinfunction "UV_2") (pintype "input"))
    )
    (net (code "223") (name "Net-(U65-~{SHDN})") (class "Default")
      (node (ref "R1") (pin "1") (pinfunction "1_1") (pintype "passive"))
      (node (ref "U65") (pin "5") (pinfunction "~{SHDN}_5") (pintype "input"))
    )
    (net (code "224") (name "unconnected-(JP1-Pad2)") (class "Default")
      (node (ref "JP1") (pin "2") (pinfunction "2_2") (pintype "passive"))
    )
    (net (code "225") (name "unconnected-(JP1-Pad4)") (class "Default")
      (node (ref "JP1") (pin "4") (pinfunction "4_4") (pintype "passive"))
    )
    (net (code "226") (name "unconnected-(JP1-Pad12)") (class "Default")
      (node (ref "JP1") (pin "12") (pinfunction "12_12") (pintype "passive"))
    )
    (net (code "227") (name "unconnected-(JP1-Pad30)") (class "Default")
      (node (ref "JP1") (pin "30") (pinfunction "30_30") (pintype "passive"))
    )
    (net (code "228") (name "unconnected-(JP2-Pad2)") (class "Default")
      (node (ref "JP2") (pin "2") (pinfunction "2_2") (pintype "passive"))
    )
    (net (code "229") (name "unconnected-(JP2-Pad4)") (class "Default")
      (node (ref "JP2") (pin "4") (pinfunction "4_4") (pintype "passive"))
    )
    (net (code "230") (name "unconnected-(JP2-Pad12)") (class "Default")
      (node (ref "JP2") (pin "12") (pinfunction "12_12") (pintype "passive"))
    )
    (net (code "231") (name "unconnected-(JP2-Pad30)") (class "Default")
      (node (ref "JP2") (pin "30") (pinfunction "30_30") (pintype "passive"))
    )
    (net (code "232") (name "unconnected-(U65-~{FAULT}-Pad6)") (class "Default")
      (node (ref "U65") (pin "6") (pinfunction "~{FAULT}_6") (pintype "output"))
    )
    (net (code "233") (name "unconnected-(U66-NC-Pad8)") (class "Default")
      (node (ref "U66") (pin "8") (pinfunction "NC_8") (pintype "no_connect"))
    )
    (net (code "234") (name "unconnected-(U66-NC2-Pad24)") (class "Default")
      (node (ref "U66") (pin "24") (pinfunction "NC2_24") (pintype "no_connect"))
    )
    (net (code "235") (name "unconnected-(U66-~{CTS}-Pad11)") (class "Default")
      (node (ref "U66") (pin "11") (pinfunction "~{CTS}_11") (pintype "bidirectional"))
    )
    (net (code "236") (name "unconnected-(U66-~{DCD}-Pad10)") (class "Default")
      (node (ref "U66") (pin "10") (pinfunction "~{DCD}_10") (pintype "bidirectional"))
    )
    (net (code "237") (name "unconnected-(U66-~{DSR}-Pad9)") (class "Default")
      (node (ref "U66") (pin "9") (pinfunction "~{DSR}_9") (pintype "bidirectional"))
    )
    (net (code "238") (name "unconnected-(U66-~{DTR}-Pad2)") (class "Default")
      (node (ref "U66") (pin "2") (pinfunction "~{DTR}_2") (pintype "bidirectional"))
    )
    (net (code "239") (name "unconnected-(U66-~{RESET}-Pad19)") (class "Default")
      (node (ref "U66") (pin "19") (pinfunction "~{RESET}_19") (pintype "passive"))
    )
    (net (code "240") (name "unconnected-(U66-~{RI}-Pad6)") (class "Default")
      (node (ref "U66") (pin "6") (pinfunction "~{RI}_6") (pintype "bidirectional"))
    )
    (net (code "241") (name "unconnected-(U66-~{RTS}-Pad3)") (class "Default")
      (node (ref "U66") (pin "3") (pinfunction "~{RTS}_3") (pintype "bidirectional"))
    )
  )
)
